# Easy_RFPA_RevA_S2.net
KiCad netlist of a schematic drawn in EAGLE
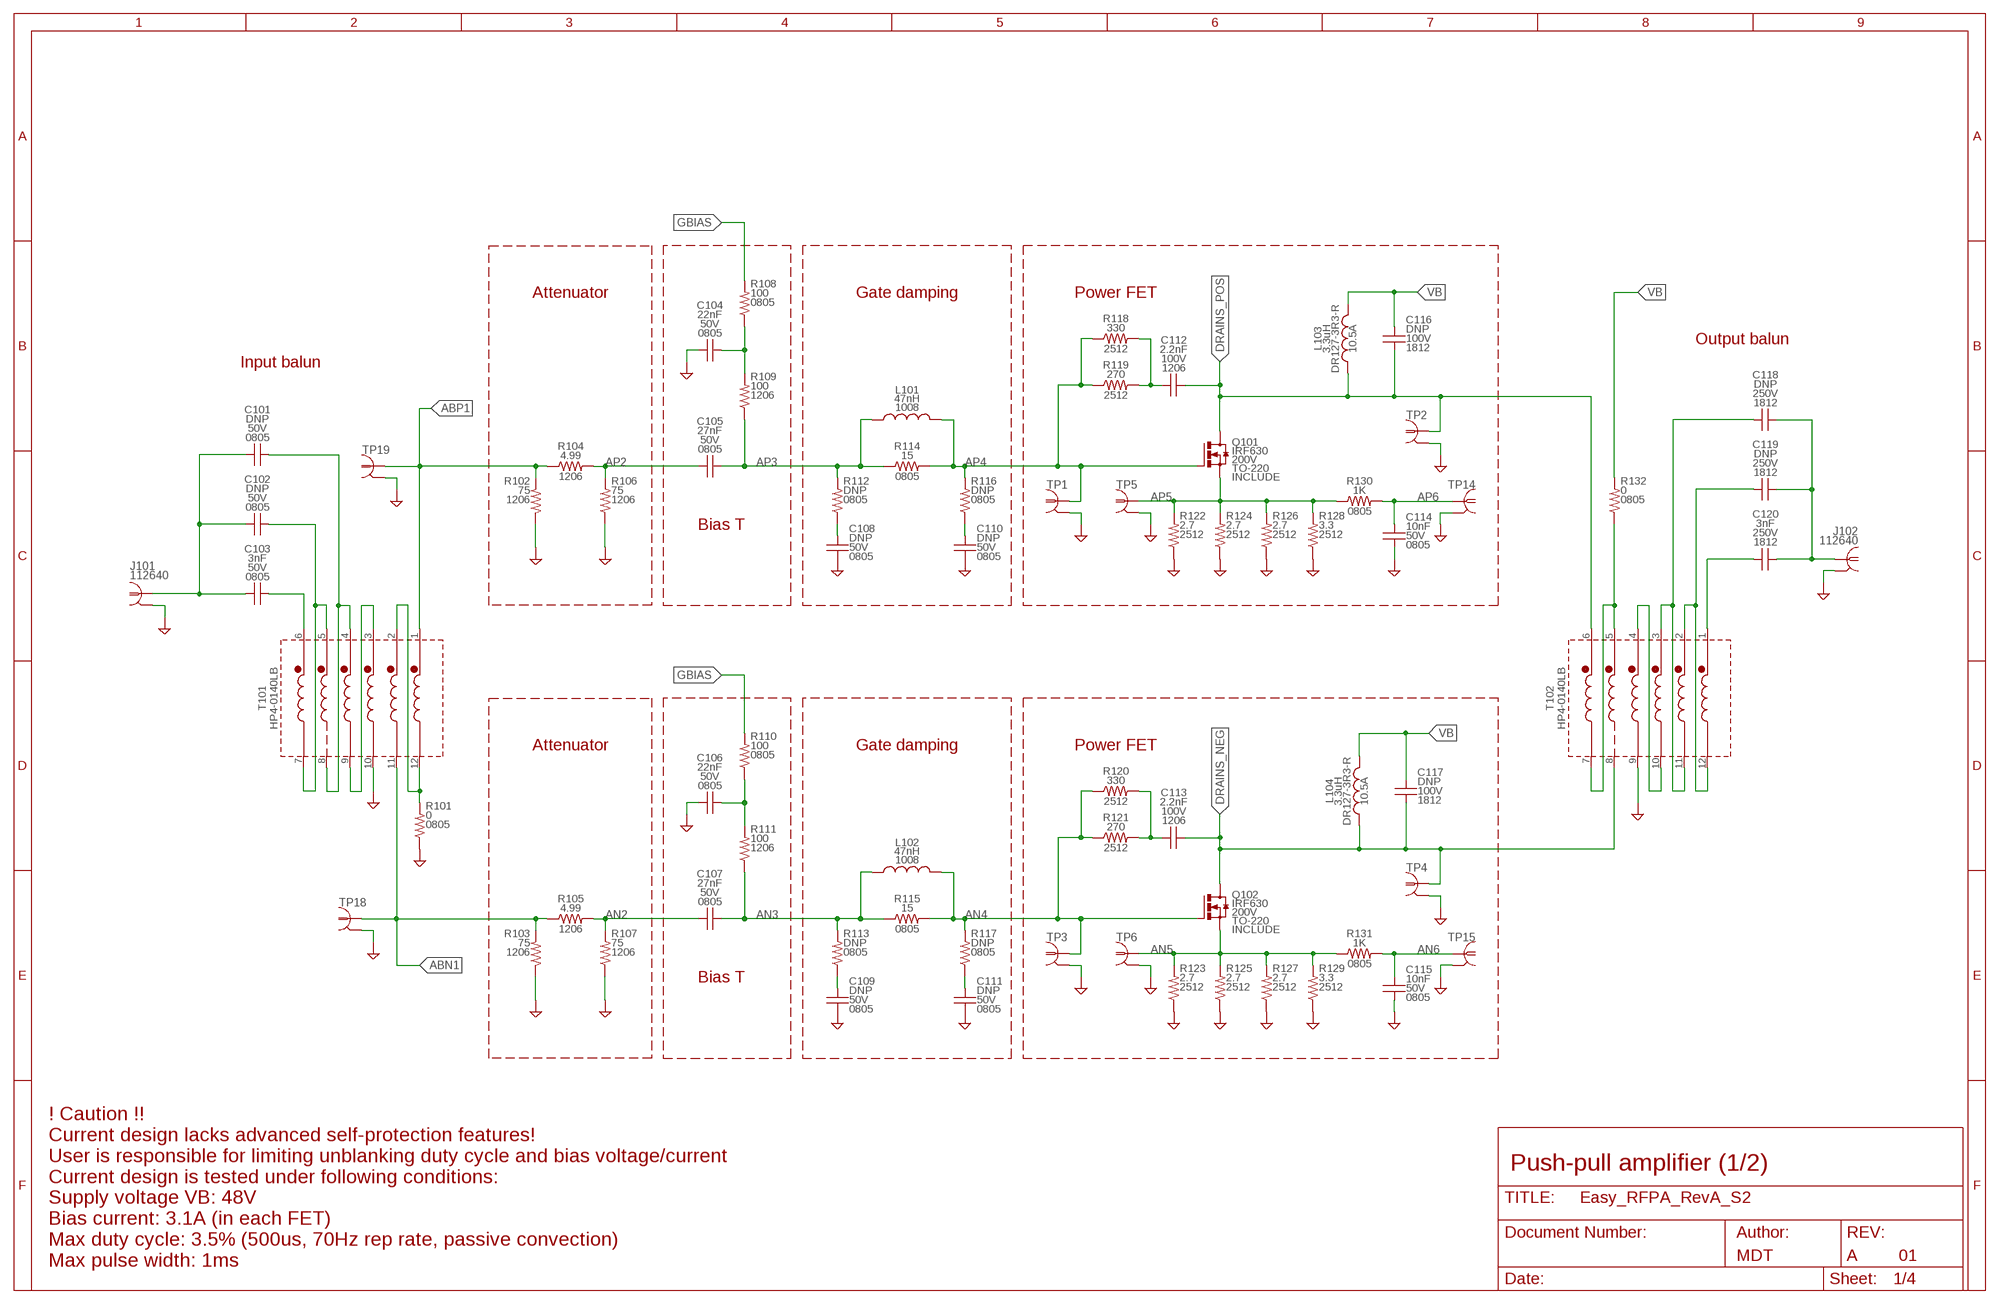
[diagram p0: schematic, sheet 1]
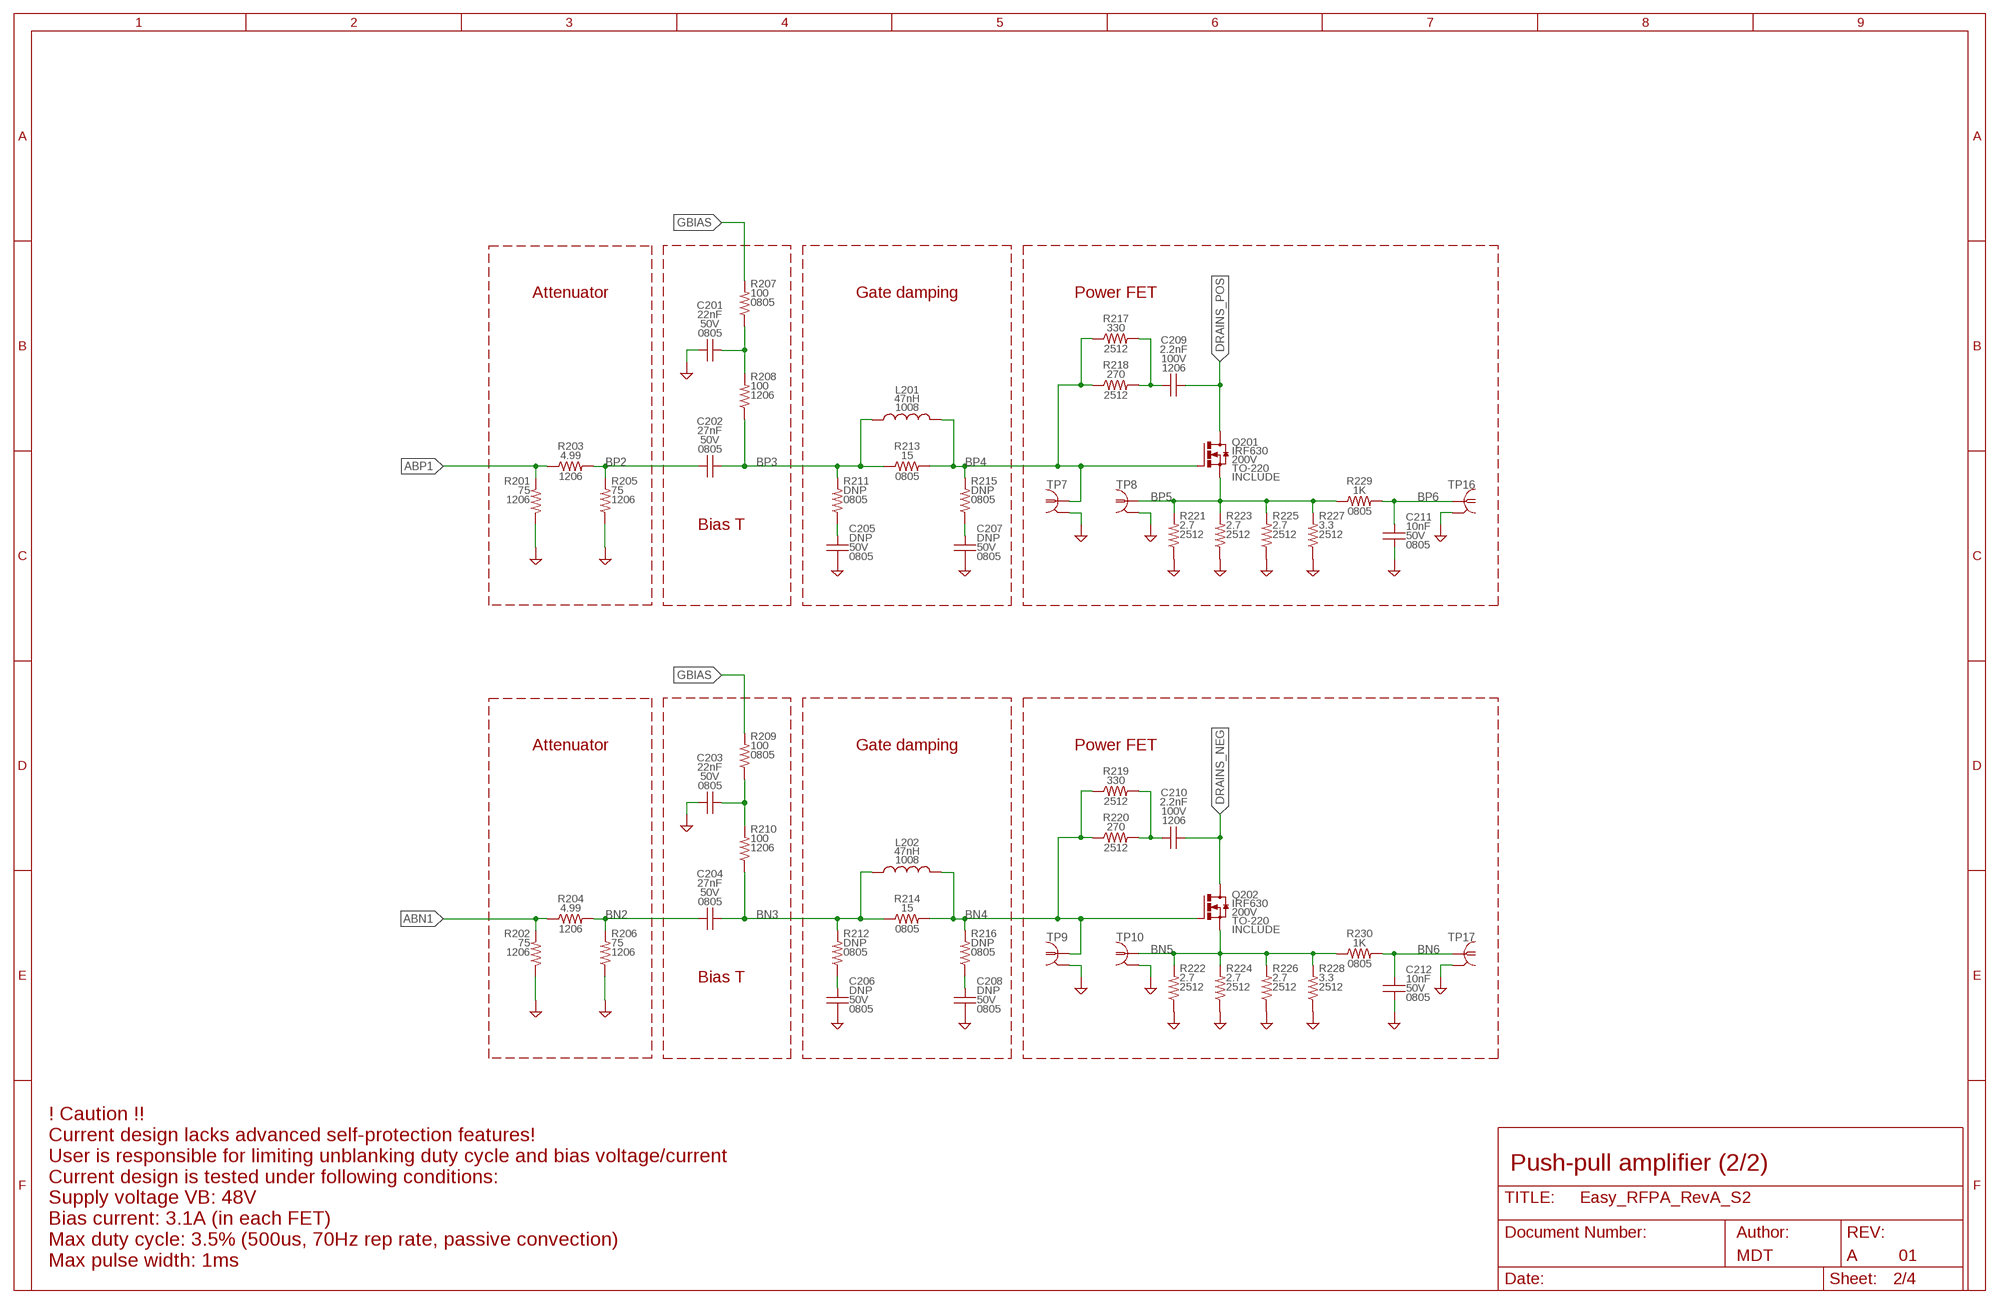
[diagram p1: schematic, sheet 2]
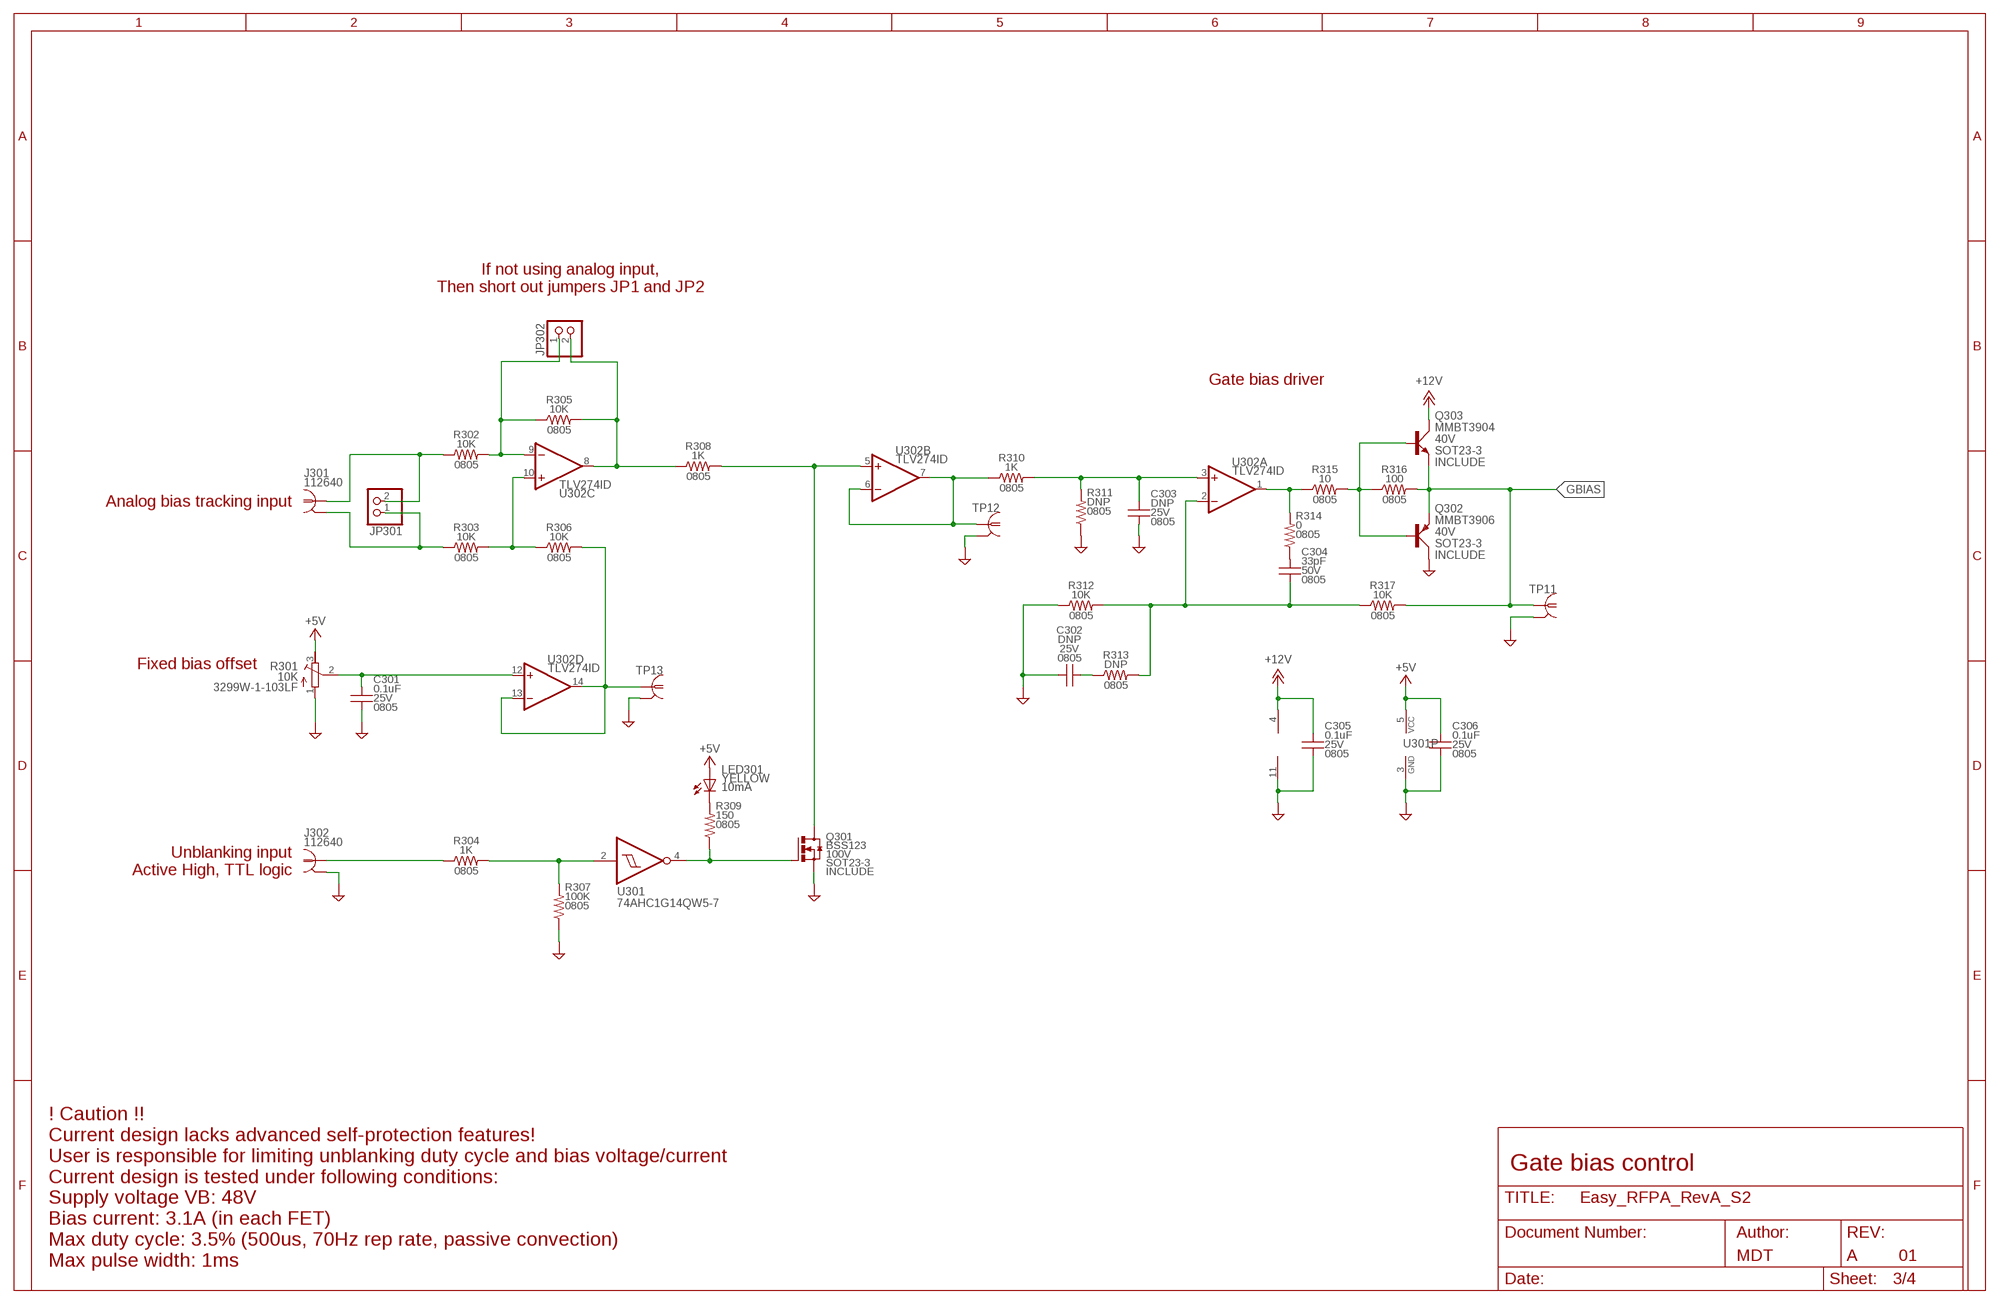
[diagram p2: schematic, sheet 3]
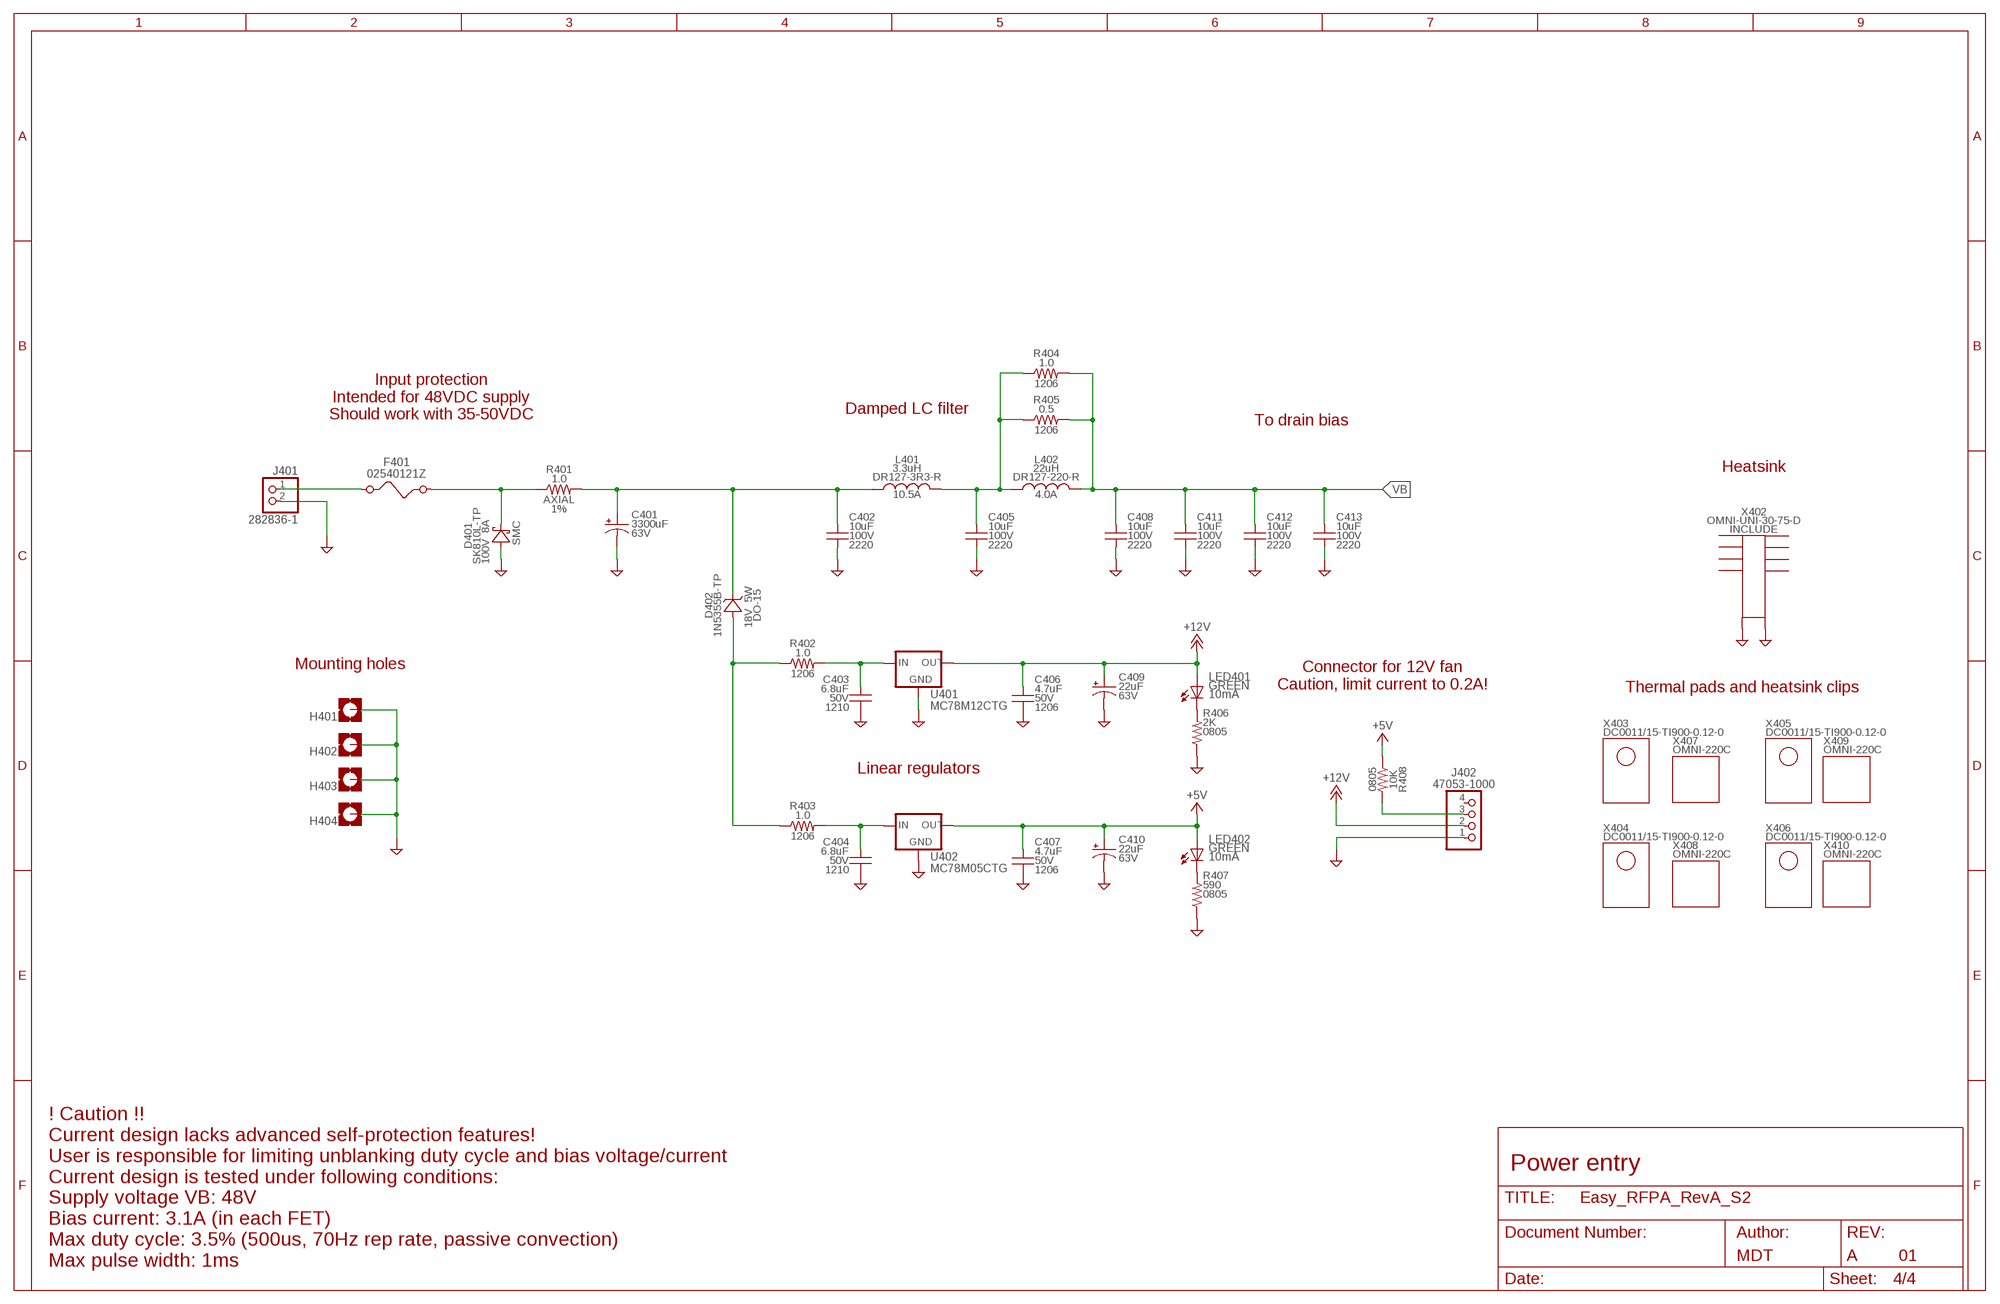
[diagram p3: schematic, sheet 4]

(export (version "E")
  (design (tool "Eeschema 10.0.6"))
  (components
    (comp (ref "C101")
      (value "DNP")
      (footprint "eagle-import:0805_IPC-7351B")
      (fields (field (name "PACKAGE") "0805") (field (name "BOM") "EXCLUDE") (field (name "VOLTAGE") "50V"))
      (libsource (lib "eagle-import") (part "C0805_IPCGEN"))
    )
    (comp (ref "C102")
      (value "DNP")
      (footprint "eagle-import:0805_IPC-7351B")
      (fields (field (name "PACKAGE") "0805") (field (name "BOM") "EXCLUDE") (field (name "VOLTAGE") "50V"))
      (libsource (lib "eagle-import") (part "C0805_IPCGEN"))
    )
    (comp (ref "C103")
      (value "3nF")
      (footprint "eagle-import:0805_IPC-7351B")
      (fields (field (name "PACKAGE") "0805") (field (name "VOLTAGE") "50V"))
      (libsource (lib "eagle-import") (part "C0805_IPCGEN"))
    )
    (comp (ref "C104")
      (value "22nF")
      (footprint "eagle-import:0805_IPC-7351B")
      (fields (field (name "BOM") "INCLUDE") (field (name "PACKAGE") "0805") (field (name "VOLTAGE") "50V"))
      (libsource (lib "eagle-import") (part "C0805_IPCGEN"))
    )
    (comp (ref "C105")
      (value "27nF")
      (footprint "eagle-import:0805_IPC-7351B")
      (fields (field (name "PACKAGE") "0805") (field (name "VOLTAGE") "50V"))
      (libsource (lib "eagle-import") (part "C0805_IPCGEN"))
    )
    (comp (ref "C106")
      (value "22nF")
      (footprint "eagle-import:0805_IPC-7351B")
      (fields (field (name "PACKAGE") "0805") (field (name "VOLTAGE") "50V"))
      (libsource (lib "eagle-import") (part "C0805_IPCGEN"))
    )
    (comp (ref "C107")
      (value "27nF")
      (footprint "eagle-import:0805_IPC-7351B")
      (fields (field (name "PACKAGE") "0805") (field (name "VOLTAGE") "50V"))
      (libsource (lib "eagle-import") (part "C0805_IPCGEN"))
    )
    (comp (ref "C108")
      (value "DNP")
      (footprint "eagle-import:0805_IPC-7351B")
      (fields (field (name "BOM") "EXCLUDE") (field (name "VOLTAGE") "50V"))
      (libsource (lib "eagle-import") (part "C0805_IPCGEN"))
    )
    (comp (ref "C109")
      (value "DNP")
      (footprint "eagle-import:0805_IPC-7351B")
      (fields (field (name "BOM") "EXCLUDE") (field (name "VOLTAGE") "50V"))
      (libsource (lib "eagle-import") (part "C0805_IPCGEN"))
    )
    (comp (ref "C110")
      (value "DNP")
      (footprint "eagle-import:0805_IPC-7351B")
      (fields (field (name "BOM") "EXCLUDE") (field (name "VOLTAGE") "50V"))
      (libsource (lib "eagle-import") (part "C0805_IPCGEN"))
    )
    (comp (ref "C111")
      (value "DNP")
      (footprint "eagle-import:0805_IPC-7351B")
      (fields (field (name "BOM") "EXCLUDE") (field (name "VOLTAGE") "50V"))
      (libsource (lib "eagle-import") (part "C0805_IPCGEN"))
    )
    (comp (ref "C112")
      (value "2.2nF")
      (footprint "eagle-import:C1206")
      (fields (field (name "PACKAGE") "1206") (field (name "VOLTAGE") "100V"))
      (libsource (lib "eagle-import") (part "CC1206GEN"))
    )
    (comp (ref "C113")
      (value "2.2nF")
      (footprint "eagle-import:C1206")
      (fields (field (name "PACKAGE") "1206") (field (name "VOLTAGE") "100V"))
      (libsource (lib "eagle-import") (part "CC1206GEN"))
    )
    (comp (ref "C114")
      (value "10nF")
      (footprint "eagle-import:0805_IPC-7351B")
      (fields (field (name "VOLTAGE") "50V"))
      (libsource (lib "eagle-import") (part "C0805_IPCGEN"))
    )
    (comp (ref "C115")
      (value "10nF")
      (footprint "eagle-import:0805_IPC-7351B")
      (fields (field (name "VOLTAGE") "50V"))
      (libsource (lib "eagle-import") (part "C0805_IPCGEN"))
    )
    (comp (ref "C116")
      (value "DNP")
      (footprint "eagle-import:C1812")
      (fields (field (name "BOM") "EXCLUDE") (field (name "VOLTAGE") "100V"))
      (libsource (lib "eagle-import") (part "CC1812GEN"))
    )
    (comp (ref "C117")
      (value "DNP")
      (footprint "eagle-import:C1812")
      (fields (field (name "BOM") "EXCLUDE") (field (name "VOLTAGE") "100V"))
      (libsource (lib "eagle-import") (part "CC1812GEN"))
    )
    (comp (ref "C118")
      (value "DNP")
      (footprint "eagle-import:C1812")
      (fields (field (name "PACKAGE") "1812") (field (name "BOM") "EXCLUDE") (field (name "VOLTAGE") "250V"))
      (libsource (lib "eagle-import") (part "CC1812GEN"))
    )
    (comp (ref "C119")
      (value "DNP")
      (footprint "eagle-import:C1812")
      (fields (field (name "PACKAGE") "1812") (field (name "BOM") "EXCLUDE") (field (name "VOLTAGE") "250V"))
      (libsource (lib "eagle-import") (part "CC1812GEN"))
    )
    (comp (ref "C120")
      (value "3nF")
      (footprint "eagle-import:C1812")
      (fields (field (name "PACKAGE") "1812") (field (name "VOLTAGE") "250V"))
      (libsource (lib "eagle-import") (part "CC1812GEN"))
    )
    (comp (ref "J101")
      (value "COAX112640BNC_EDGE")
      (footprint "eagle-import:BNC_EDGE")
      (fields (field (name "PARTNO") "112640"))
      (libsource (lib "eagle-import") (part "COAXBNC_EDGE112640"))
    )
    (comp (ref "J102")
      (value "COAX112640BNC_EDGE")
      (footprint "eagle-import:BNC_EDGE")
      (fields (field (name "PARTNO") "112640"))
      (libsource (lib "eagle-import") (part "COAXBNC_EDGE112640"))
    )
    (comp (ref "L101")
      (value "47nH")
      (footprint "eagle-import:L1008")
      (fields (field (name "PARTNO") "1008CS-470XJLC"))
      (libsource (lib "eagle-import") (part "L_CHIP1008L-47N-AIR-5%-1008-1A"))
    )
    (comp (ref "L102")
      (value "47nH")
      (footprint "eagle-import:L1008")
      (fields (field (name "PARTNO") "1008CS-470XJLC"))
      (libsource (lib "eagle-import") (part "L_CHIP1008L-47N-AIR-5%-1008-1A"))
    )
    (comp (ref "L103")
      (value "3.3uH")
      (footprint "eagle-import:DR127")
      (fields (field (name "PARTNO") "DR127-3R3-R"))
      (libsource (lib "eagle-import") (part "LL-3.3U-FERRITE-20%-12.5X12.5MM-10.5A"))
    )
    (comp (ref "L104")
      (value "3.3uH")
      (footprint "eagle-import:DR127")
      (fields (field (name "PARTNO") "DR127-3R3-R"))
      (libsource (lib "eagle-import") (part "LL-3.3U-FERRITE-20%-12.5X12.5MM-10.5A"))
    )
    (comp (ref "Q101")
      (value "IRF630")
      (footprint "eagle-import:TO220BV")
      (fields (field (name "VOLTAGE") "200V"))
      (libsource (lib "eagle-import") (part "MOSFET_NTO-220-VERTIRF630"))
    )
    (comp (ref "Q102")
      (value "IRF630")
      (footprint "eagle-import:TO220BV")
      (fields (field (name "VOLTAGE") "200V"))
      (libsource (lib "eagle-import") (part "MOSFET_NTO-220-VERTIRF630"))
    )
    (comp (ref "R101")
      (value "0")
      (footprint "eagle-import:0805_IPC-7351B")
      (libsource (lib "eagle-import") (part "R0805_IPCGEN"))
    )
    (comp (ref "R102")
      (value "75")
      (footprint "eagle-import:1206_IPC-7351B")
      (libsource (lib "eagle-import") (part "R1206_IPCGEN"))
    )
    (comp (ref "R103")
      (value "75")
      (footprint "eagle-import:1206_IPC-7351B")
      (libsource (lib "eagle-import") (part "R1206_IPCGEN"))
    )
    (comp (ref "R104")
      (value "4.99")
      (footprint "eagle-import:1206_IPC-7351B")
      (libsource (lib "eagle-import") (part "R901206_IPCGEN"))
    )
    (comp (ref "R105")
      (value "4.99")
      (footprint "eagle-import:1206_IPC-7351B")
      (libsource (lib "eagle-import") (part "R901206_IPCGEN"))
    )
    (comp (ref "R106")
      (value "75")
      (footprint "eagle-import:1206_IPC-7351B")
      (libsource (lib "eagle-import") (part "R1206_IPCGEN"))
    )
    (comp (ref "R107")
      (value "75")
      (footprint "eagle-import:1206_IPC-7351B")
      (libsource (lib "eagle-import") (part "R1206_IPCGEN"))
    )
    (comp (ref "R108")
      (value "100")
      (footprint "eagle-import:0805_IPC-7351B")
      (libsource (lib "eagle-import") (part "R0805_IPCGEN"))
    )
    (comp (ref "R109")
      (value "100")
      (footprint "eagle-import:1206_IPC-7351B")
      (libsource (lib "eagle-import") (part "R1206_IPCGEN"))
    )
    (comp (ref "R110")
      (value "100")
      (footprint "eagle-import:0805_IPC-7351B")
      (libsource (lib "eagle-import") (part "R0805_IPCGEN"))
    )
    (comp (ref "R111")
      (value "100")
      (footprint "eagle-import:1206_IPC-7351B")
      (libsource (lib "eagle-import") (part "R1206_IPCGEN"))
    )
    (comp (ref "R112")
      (value "DNP")
      (footprint "eagle-import:0805_IPC-7351B")
      (fields (field (name "BOM") "EXCLUDE"))
      (libsource (lib "eagle-import") (part "R0805_IPCGEN"))
    )
    (comp (ref "R113")
      (value "DNP")
      (footprint "eagle-import:0805_IPC-7351B")
      (fields (field (name "BOM") "EXCLUDE"))
      (libsource (lib "eagle-import") (part "R0805_IPCGEN"))
    )
    (comp (ref "R114")
      (value "15")
      (footprint "eagle-import:0805_IPC-7351B")
      (libsource (lib "eagle-import") (part "R900805_IPCGEN"))
    )
    (comp (ref "R115")
      (value "15")
      (footprint "eagle-import:0805_IPC-7351B")
      (libsource (lib "eagle-import") (part "R900805_IPCGEN"))
    )
    (comp (ref "R116")
      (value "DNP")
      (footprint "eagle-import:0805_IPC-7351B")
      (fields (field (name "BOM") "EXCLUDE"))
      (libsource (lib "eagle-import") (part "R0805_IPCGEN"))
    )
    (comp (ref "R117")
      (value "DNP")
      (footprint "eagle-import:0805_IPC-7351B")
      (fields (field (name "BOM") "EXCLUDE"))
      (libsource (lib "eagle-import") (part "R0805_IPCGEN"))
    )
    (comp (ref "R118")
      (value "330")
      (footprint "eagle-import:R2512")
      (libsource (lib "eagle-import") (part "R90R2512GEN"))
    )
    (comp (ref "R119")
      (value "270")
      (footprint "eagle-import:R2512")
      (libsource (lib "eagle-import") (part "R90R2512GEN"))
    )
    (comp (ref "R120")
      (value "330")
      (footprint "eagle-import:R2512")
      (libsource (lib "eagle-import") (part "R90R2512GEN"))
    )
    (comp (ref "R121")
      (value "270")
      (footprint "eagle-import:R2512")
      (libsource (lib "eagle-import") (part "R90R2512GEN"))
    )
    (comp (ref "R122")
      (value "2.7")
      (footprint "eagle-import:R2512")
      (libsource (lib "eagle-import") (part "RR2512GEN"))
    )
    (comp (ref "R123")
      (value "2.7")
      (footprint "eagle-import:R2512")
      (libsource (lib "eagle-import") (part "RR2512GEN"))
    )
    (comp (ref "R124")
      (value "2.7")
      (footprint "eagle-import:R2512")
      (libsource (lib "eagle-import") (part "RR2512GEN"))
    )
    (comp (ref "R125")
      (value "2.7")
      (footprint "eagle-import:R2512")
      (libsource (lib "eagle-import") (part "RR2512GEN"))
    )
    (comp (ref "R126")
      (value "2.7")
      (footprint "eagle-import:R2512")
      (libsource (lib "eagle-import") (part "RR2512GEN"))
    )
    (comp (ref "R127")
      (value "2.7")
      (footprint "eagle-import:R2512")
      (libsource (lib "eagle-import") (part "RR2512GEN"))
    )
    (comp (ref "R128")
      (value "3.3")
      (footprint "eagle-import:R2512")
      (libsource (lib "eagle-import") (part "RR2512GEN"))
    )
    (comp (ref "R129")
      (value "3.3")
      (footprint "eagle-import:R2512")
      (libsource (lib "eagle-import") (part "RR2512GEN"))
    )
    (comp (ref "R130")
      (value "1K")
      (footprint "eagle-import:0805_IPC-7351B")
      (libsource (lib "eagle-import") (part "R900805_IPCGEN"))
    )
    (comp (ref "R131")
      (value "1K")
      (footprint "eagle-import:0805_IPC-7351B")
      (libsource (lib "eagle-import") (part "R900805_IPCGEN"))
    )
    (comp (ref "R132")
      (value "0")
      (footprint "eagle-import:0805_IPC-7351B")
      (libsource (lib "eagle-import") (part "R0805_IPCGEN"))
    )
    (comp (ref "T101")
      (value "HP4_TRAFO")
      (footprint "eagle-import:HP4")
      (fields (field (name "PARTNO") "HP4-0140LB"))
      (libsource (lib "eagle-import") (part "HP4_TRAFO"))
    )
    (comp (ref "T102")
      (value "HP4_TRAFO")
      (footprint "eagle-import:HP4")
      (fields (field (name "PARTNO") "HP4-0140LB"))
      (libsource (lib "eagle-import") (part "HP4_TRAFO"))
    )
    (comp (ref "TP1")
      (value "PROBE_TPTP_5MM")
      (footprint "eagle-import:PROBE_TP_5MM")
      (libsource (lib "eagle-import") (part "PROBE_TPTP_5MM"))
    )
    (comp (ref "TP2")
      (value "PROBE_TPTP_7P5MM")
      (footprint "eagle-import:PROBE_TP_7P5MM")
      (libsource (lib "eagle-import") (part "PROBE_TPTP_7P5MM"))
    )
    (comp (ref "TP3")
      (value "PROBE_TPTP_5MM")
      (footprint "eagle-import:PROBE_TP_5MM")
      (libsource (lib "eagle-import") (part "PROBE_TPTP_5MM"))
    )
    (comp (ref "TP4")
      (value "PROBE_TPTP_7P5MM")
      (footprint "eagle-import:PROBE_TP_7P5MM")
      (libsource (lib "eagle-import") (part "PROBE_TPTP_7P5MM"))
    )
    (comp (ref "TP5")
      (value "PROBE_TPTP_7P5MM")
      (footprint "eagle-import:PROBE_TP_7P5MM")
      (libsource (lib "eagle-import") (part "PROBE_TPTP_7P5MM"))
    )
    (comp (ref "TP6")
      (value "PROBE_TPTP_7P5MM")
      (footprint "eagle-import:PROBE_TP_7P5MM")
      (libsource (lib "eagle-import") (part "PROBE_TPTP_7P5MM"))
    )
    (comp (ref "TP14")
      (value "PROBE_TPTP_5MM")
      (footprint "eagle-import:PROBE_TP_5MM")
      (libsource (lib "eagle-import") (part "PROBE_TPTP_5MM"))
    )
    (comp (ref "TP15")
      (value "PROBE_TPTP_5MM")
      (footprint "eagle-import:PROBE_TP_5MM")
      (libsource (lib "eagle-import") (part "PROBE_TPTP_5MM"))
    )
    (comp (ref "TP18")
      (value "PROBE_TPTP_5MM")
      (footprint "eagle-import:PROBE_TP_5MM")
      (libsource (lib "eagle-import") (part "PROBE_TPTP_5MM"))
    )
    (comp (ref "TP19")
      (value "PROBE_TPTP_5MM")
      (footprint "eagle-import:PROBE_TP_5MM")
      (libsource (lib "eagle-import") (part "PROBE_TPTP_5MM"))
    )
    (comp (ref "C401")
      (value "3300uF")
      (footprint "eagle-import:EB25D")
      (fields (field (name "PARTNO") "MAL225638332E3") (field (name "VOLTAGE") "63V"))
      (libsource (lib "eagle-import") (part "CPOLEB25DC-3300U-63V-20%-25DX37L-ELEC"))
    )
    (comp (ref "C402")
      (value "10uF")
      (footprint "eagle-import:C2220_CKG57N")
      (fields
        (field (name "BOM") "INCLUDE")
        (field (name "PACKAGE") "2220")
        (field (name "PARTNO") "CGA9N3X7S2A106M230KE")
        (field (name "VOLTAGE") "100V")
      )
      (libsource (lib "eagle-import") (part "CC2220_CKG57NCC-10U-100V-20%-2220-X7T"))
    )
    (comp (ref "C403")
      (value "6.8uF")
      (footprint "eagle-import:C1210")
      (fields (field (name "DIALECTRIC") "X7S") (field (name "VOLTAGE") "50V"))
      (libsource (lib "eagle-import") (part "CC1210GEN"))
    )
    (comp (ref "C404")
      (value "6.8uF")
      (footprint "eagle-import:C1210")
      (fields (field (name "DIALECTRIC") "X7S") (field (name "VOLTAGE") "50V"))
      (libsource (lib "eagle-import") (part "CC1210GEN"))
    )
    (comp (ref "C405")
      (value "10uF")
      (footprint "eagle-import:C2220_CKG57N")
      (fields
        (field (name "BOM") "INCLUDE")
        (field (name "PACKAGE") "2220")
        (field (name "PARTNO") "CGA9N3X7S2A106M230KE")
        (field (name "VOLTAGE") "100V")
      )
      (libsource (lib "eagle-import") (part "CC2220_CKG57NCC-10U-100V-20%-2220-X7T"))
    )
    (comp (ref "C406")
      (value "4.7uF")
      (footprint "eagle-import:C1206")
      (fields (field (name "DIALECTRIC") "X7R") (field (name "VOLTAGE") "50V"))
      (libsource (lib "eagle-import") (part "CC1206GEN"))
    )
    (comp (ref "C407")
      (value "4.7uF")
      (footprint "eagle-import:C1206")
      (fields (field (name "DIALECTRIC") "X7R") (field (name "VOLTAGE") "50V"))
      (libsource (lib "eagle-import") (part "CC1206GEN"))
    )
    (comp (ref "C408")
      (value "10uF")
      (footprint "eagle-import:C2220_CKG57N")
      (fields (field (name "PARTNO") "CGA9N3X7S2A106M230KE") (field (name "VOLTAGE") "100V"))
      (libsource (lib "eagle-import") (part "CC2220_CKG57NCC-10U-100V-20%-2220-X7T"))
    )
    (comp (ref "C409")
      (value "22uF")
      (footprint "eagle-import:E2,5-7")
      (fields (field (name "PARTNO") "860010773010") (field (name "VOLTAGE") "63V"))
      (libsource (lib "eagle-import") (part "CPOLE2,5-7C-22U-63V-20%-6.3DX12.5L-ELEC"))
    )
    (comp (ref "C410")
      (value "22uF")
      (footprint "eagle-import:E2,5-7")
      (fields (field (name "PARTNO") "860010773010") (field (name "VOLTAGE") "63V"))
      (libsource (lib "eagle-import") (part "CPOLE2,5-7C-22U-63V-20%-6.3DX12.5L-ELEC"))
    )
    (comp (ref "C411")
      (value "10uF")
      (footprint "eagle-import:C2220_CKG57N")
      (fields (field (name "PARTNO") "CGA9N3X7S2A106M230KE") (field (name "VOLTAGE") "100V"))
      (libsource (lib "eagle-import") (part "CC2220_CKG57NCC-10U-100V-20%-2220-X7T"))
    )
    (comp (ref "C412")
      (value "10uF")
      (footprint "eagle-import:C2220_CKG57N")
      (fields (field (name "PARTNO") "CGA9N3X7S2A106M230KE") (field (name "VOLTAGE") "100V"))
      (libsource (lib "eagle-import") (part "CC2220_CKG57NCC-10U-100V-20%-2220-X7T"))
    )
    (comp (ref "C413")
      (value "10uF")
      (footprint "eagle-import:C2220_CKG57N")
      (fields (field (name "PARTNO") "CGA9N3X7S2A106M230KE") (field (name "VOLTAGE") "100V"))
      (libsource (lib "eagle-import") (part "CC2220_CKG57NCC-10U-100V-20%-2220-X7T"))
    )
    (comp (ref "D401")
      (value "D-SCHOTTKYSK810L-TPSMC")
      (footprint "eagle-import:DO-214AB(SMC)")
      (fields (field (name "PARTNO") "SK810L-TP") (field (name "VOLTAGE") "100V"))
      (libsource (lib "eagle-import") (part "D-SCHOTTKYSMCSK810L-TP"))
    )
    (comp (ref "D402")
      (value "D-ZENER1N5355B-TPDO15-12")
      (footprint "eagle-import:DO15-12")
      (fields (field (name "PARTNO") "1N5355B-TP") (field (name "POWER") "5W") (field (name "VOLTAGE") "18V"))
      (libsource (lib "eagle-import") (part "D-ZENERDO15-121N5355B-TP"))
    )
    (comp (ref "F401")
      (value "FUSE_2P")
      (footprint "eagle-import:02540121Z")
      (fields (field (name "PARTNO") "02540121Z"))
      (libsource (lib "eagle-import") (part "FUSE_2P"))
    )
    (comp (ref "H401")
      (value "MOUNT-PAD-SQUARE3.2")
      (footprint "eagle-import:3,2-PAD-SQUARE")
      (libsource (lib "eagle-import") (part "MOUNT-PAD-SQUARE3.2"))
    )
    (comp (ref "H402")
      (value "MOUNT-PAD-SQUARE3.2")
      (footprint "eagle-import:3,2-PAD-SQUARE")
      (libsource (lib "eagle-import") (part "MOUNT-PAD-SQUARE3.2"))
    )
    (comp (ref "H403")
      (value "MOUNT-PAD-SQUARE3.2")
      (footprint "eagle-import:3,2-PAD-SQUARE")
      (libsource (lib "eagle-import") (part "MOUNT-PAD-SQUARE3.2"))
    )
    (comp (ref "H404")
      (value "MOUNT-PAD-SQUARE3.2")
      (footprint "eagle-import:3,2-PAD-SQUARE")
      (libsource (lib "eagle-import") (part "MOUNT-PAD-SQUARE3.2"))
    )
    (comp (ref "J401")
      (value "HDR_2X1282836-1282836-1")
      (footprint "eagle-import:W237-02")
      (fields (field (name "PARTNO") "282836-1"))
      (libsource (lib "eagle-import") (part "HDR_2X1282836-1282836-1"))
    )
    (comp (ref "J402")
      (value "KK_PCFAN")
      (footprint "eagle-import:47053-1000")
      (fields (field (name "PARTNO") "47053-1000"))
      (libsource (lib "eagle-import") (part "KK_PCFAN"))
    )
    (comp (ref "L401")
      (value "3.3uH")
      (footprint "eagle-import:DR127")
      (fields (field (name "PARTNO") "DR127-3R3-R"))
      (libsource (lib "eagle-import") (part "LL-3.3U-FERRITE-20%-12.5X12.5MM-10.5A"))
    )
    (comp (ref "L402")
      (value "22uH")
      (footprint "eagle-import:DR127")
      (fields (field (name "PARTNO") "DR127-220-R"))
      (libsource (lib "eagle-import") (part "LL-22U-FERRITE-20%-12.5X12.5MM-4A"))
    )
    (comp (ref "LED401")
      (value "LEDHLMP-3962-F0002T1_3/4")
      (footprint "eagle-import:LED5MM")
      (fields (field (name "PARTNO") "HLMP-3962-F0002"))
      (libsource (lib "eagle-import") (part "LEDT1_3/4HLMP-3962-F0002"))
    )
    (comp (ref "LED402")
      (value "LEDHLMP-3962-F0002T1_3/4")
      (footprint "eagle-import:LED5MM")
      (fields (field (name "PARTNO") "HLMP-3962-F0002"))
      (libsource (lib "eagle-import") (part "LEDT1_3/4HLMP-3962-F0002"))
    )
    (comp (ref "R401")
      (value "1.0")
      (footprint "eagle-import:P0817V")
      (fields (field (name "PARTNO") "PAC300001008FAC000") (field (name "POWER") "3W"))
      (libsource (lib "eagle-import") (part "R90P0817VR-1.0-1%-AXIAL-3W"))
    )
    (comp (ref "R402")
      (value "1.0")
      (footprint "eagle-import:R1206")
      (libsource (lib "eagle-import") (part "R90R1206GEN"))
    )
    (comp (ref "R403")
      (value "1.0")
      (footprint "eagle-import:R1206")
      (libsource (lib "eagle-import") (part "R90R1206GEN"))
    )
    (comp (ref "R404")
      (value "1.0")
      (footprint "eagle-import:1206_IPC-7351B")
      (libsource (lib "eagle-import") (part "R901206_IPCGEN"))
    )
    (comp (ref "R405")
      (value "0.5")
      (footprint "eagle-import:1206_IPC-7351B")
      (libsource (lib "eagle-import") (part "R901206_IPCGEN"))
    )
    (comp (ref "R406")
      (value "2K")
      (footprint "eagle-import:0805_IPC-7351B")
      (libsource (lib "eagle-import") (part "R0805_IPCGEN"))
    )
    (comp (ref "R407")
      (value "590")
      (footprint "eagle-import:0805_IPC-7351B")
      (libsource (lib "eagle-import") (part "R0805_IPCGEN"))
    )
    (comp (ref "R408")
      (value "10K")
      (footprint "eagle-import:0805_IPC-7351B")
      (libsource (lib "eagle-import") (part "R900805_IPCGEN"))
    )
    (comp (ref "U401")
      (value "LDO_3TERMMC78M12CTGTO220_VERT")
      (footprint "eagle-import:TO220BV")
      (fields (field (name "PARTNO") "MC78M12CTG"))
      (libsource (lib "eagle-import") (part "LDO_3TERMTO220_VERTMC78M12CTG"))
    )
    (comp (ref "U402")
      (value "LDO_3TERMMC78M05CTGTO220_VERT")
      (footprint "eagle-import:TO220BV")
      (fields (field (name "PARTNO") "MC78M05CTG"))
      (libsource (lib "eagle-import") (part "LDO_3TERMTO220_VERTMC78M05CTG"))
    )
    (comp (ref "X402")
      (value "HEATSINK_OMNI_DUALOMNI-UNI-30-75-D30-75-D")
      (footprint "eagle-import:OMNI-UNI-30-75-D")
      (fields (field (name "PARTNO") "OMNI-UNI-30-75-D"))
      (libsource (lib "eagle-import") (part "HEATSINK_OMNI_DUAL30-75-DOMNI-UNI-30-75-D"))
    )
    (comp (ref "C301")
      (value "0.1uF")
      (footprint "eagle-import:0805_IPC-7351B")
      (fields (field (name "VOLTAGE") "25V"))
      (libsource (lib "eagle-import") (part "C0805_IPCGEN"))
    )
    (comp (ref "C302")
      (value "DNP")
      (footprint "eagle-import:0805_IPC-7351B")
      (fields (field (name "PACKAGE") "0805") (field (name "BOM") "EXCLUDE") (field (name "VOLTAGE") "25V"))
      (libsource (lib "eagle-import") (part "C0805_IPCGEN"))
    )
    (comp (ref "C303")
      (value "DNP")
      (footprint "eagle-import:0805_IPC-7351B")
      (fields (field (name "BOM") "EXCLUDE") (field (name "VOLTAGE") "25V"))
      (libsource (lib "eagle-import") (part "C0805_IPCGEN"))
    )
    (comp (ref "C304")
      (value "33pF")
      (footprint "eagle-import:0805_IPC-7351B")
      (fields (field (name "VOLTAGE") "50V"))
      (libsource (lib "eagle-import") (part "C0805_IPCGEN"))
    )
    (comp (ref "C305")
      (value "0.1uF")
      (footprint "eagle-import:0805_IPC-7351B")
      (fields (field (name "VOLTAGE") "25V"))
      (libsource (lib "eagle-import") (part "C0805_IPCGEN"))
    )
    (comp (ref "C306")
      (value "0.1uF")
      (footprint "eagle-import:0805_IPC-7351B")
      (fields (field (name "VOLTAGE") "25V"))
      (libsource (lib "eagle-import") (part "C0805_IPCGEN"))
    )
    (comp (ref "J301")
      (value "COAX112640BNC_EDGE")
      (footprint "eagle-import:BNC_EDGE")
      (fields (field (name "PARTNO") "112640"))
      (libsource (lib "eagle-import") (part "COAXBNC_EDGE112640"))
    )
    (comp (ref "J302")
      (value "COAX112640BNC_EDGE")
      (footprint "eagle-import:BNC_EDGE")
      (fields (field (name "PARTNO") "112640"))
      (libsource (lib "eagle-import") (part "COAXBNC_EDGE112640"))
    )
    (comp (ref "JP301")
      (value "PINHD-1X2")
      (footprint "eagle-import:1X02")
      (libsource (lib "eagle-import") (part "PINHD-1X2"))
    )
    (comp (ref "JP302")
      (value "PINHD-1X2")
      (footprint "eagle-import:1X02")
      (libsource (lib "eagle-import") (part "PINHD-1X2"))
    )
    (comp (ref "LED301")
      (value "LEDHLMP-3401-E0002T1_3/4")
      (footprint "eagle-import:LED5MM")
      (fields (field (name "PARTNO") " HLMP-3401-E0002"))
      (libsource (lib "eagle-import") (part "LEDT1_3/4HLMP-3401-E0002"))
    )
    (comp (ref "Q301")
      (value "MOSFET_NBSS123SOT23")
      (footprint "eagle-import:SOT23R_INFINEON")
      (fields (field (name "PARTNO") "BSS123-7-F") (field (name "VOLTAGE") "100V"))
      (libsource (lib "eagle-import") (part "MOSFET_NSOT23BSS123"))
    )
    (comp (ref "Q302")
      (value "PNPSOT23_BEC")
      (footprint "eagle-import:SOT23R_INFINEON")
      (fields (field (name "VOLTAGE") "40V") (field (name "PARTNO") "PMBT3906,215"))
      (libsource (lib "eagle-import") (part "PNPSOT23_BEC"))
    )
    (comp (ref "Q303")
      (value "NPNMMBT3904SOT23_BEC")
      (footprint "eagle-import:SOT23R_INFINEON")
      (fields (field (name "PARTNO") "MMBT3904,215") (field (name "VOLTAGE") "40V"))
      (libsource (lib "eagle-import") (part "NPNSOT23_BECMMBT3904"))
    )
    (comp (ref "R301")
      (value "10K")
      (footprint "eagle-import:RTRIM3299W")
      (fields (field (name "PARTNO") "3299W-1-103LF") (field (name "POWER") "0.5W"))
      (libsource (lib "eagle-import") (part "RTRIM3299WRTRIM-10K-10%-3299W-0.5W"))
    )
    (comp (ref "R302")
      (value "10K")
      (footprint "eagle-import:0805_IPC-7351B")
      (libsource (lib "eagle-import") (part "R900805_IPCGEN"))
    )
    (comp (ref "R303")
      (value "10K")
      (footprint "eagle-import:0805_IPC-7351B")
      (libsource (lib "eagle-import") (part "R900805_IPCGEN"))
    )
    (comp (ref "R304")
      (value "1K")
      (footprint "eagle-import:0805_IPC-7351B")
      (libsource (lib "eagle-import") (part "R900805_IPCGEN"))
    )
    (comp (ref "R305")
      (value "10K")
      (footprint "eagle-import:0805_IPC-7351B")
      (libsource (lib "eagle-import") (part "R900805_IPCGEN"))
    )
    (comp (ref "R306")
      (value "10K")
      (footprint "eagle-import:0805_IPC-7351B")
      (libsource (lib "eagle-import") (part "R900805_IPCGEN"))
    )
    (comp (ref "R307")
      (value "100K")
      (footprint "eagle-import:0805_IPC-7351B")
      (libsource (lib "eagle-import") (part "R0805_IPCGEN"))
    )
    (comp (ref "R308")
      (value "1K")
      (footprint "eagle-import:0805_IPC-7351B")
      (libsource (lib "eagle-import") (part "R900805_IPCGEN"))
    )
    (comp (ref "R309")
      (value "150")
      (footprint "eagle-import:0805_IPC-7351B")
      (libsource (lib "eagle-import") (part "R0805_IPCGEN"))
    )
    (comp (ref "R310")
      (value "1K")
      (footprint "eagle-import:0805_IPC-7351B")
      (libsource (lib "eagle-import") (part "R900805_IPCGEN"))
    )
    (comp (ref "R311")
      (value "DNP")
      (footprint "eagle-import:0805_IPC-7351B")
      (fields (field (name "BOM") "EXCLUDE"))
      (libsource (lib "eagle-import") (part "R0805_IPCGEN"))
    )
    (comp (ref "R312")
      (value "10K")
      (footprint "eagle-import:0805_IPC-7351B")
      (libsource (lib "eagle-import") (part "R900805_IPCGEN"))
    )
    (comp (ref "R313")
      (value "DNP")
      (footprint "eagle-import:0805_IPC-7351B")
      (fields (field (name "BOM") "EXCLUDE"))
      (libsource (lib "eagle-import") (part "R900805_IPCGEN"))
    )
    (comp (ref "R314")
      (value "0")
      (footprint "eagle-import:0805_IPC-7351B")
      (libsource (lib "eagle-import") (part "R0805_IPCGEN"))
    )
    (comp (ref "R315")
      (value "10")
      (footprint "eagle-import:0805_IPC-7351B")
      (libsource (lib "eagle-import") (part "R900805_IPCGEN"))
    )
    (comp (ref "R316")
      (value "100")
      (footprint "eagle-import:0805_IPC-7351B")
      (libsource (lib "eagle-import") (part "R900805_IPCGEN"))
    )
    (comp (ref "R317")
      (value "10K")
      (footprint "eagle-import:0805_IPC-7351B")
      (libsource (lib "eagle-import") (part "R900805_IPCGEN"))
    )
    (comp (ref "TP11")
      (value "PROBE_TPTP_5MM")
      (footprint "eagle-import:PROBE_TP_5MM")
      (libsource (lib "eagle-import") (part "PROBE_TPTP_5MM"))
    )
    (comp (ref "TP12")
      (value "PROBE_TPTP_5MM")
      (footprint "eagle-import:PROBE_TP_5MM")
      (libsource (lib "eagle-import") (part "PROBE_TPTP_5MM"))
    )
    (comp (ref "TP13")
      (value "PROBE_TPTP_5MM")
      (footprint "eagle-import:PROBE_TP_5MM")
      (libsource (lib "eagle-import") (part "PROBE_TPTP_5MM"))
    )
    (comp (ref "U301")
      (value "74AHC1G14DBV")
      (footprint "eagle-import:SOT23-5")
      (description "IC INVERT SCHMITT 1CH 1-IN SOT25")
      (fields
        (field (name "PARTNO") "74AHC1G14QW5-7")
        (field (name "BOM") "INCLUDE")
        (field (name "PACKAGE") "SOT23-5")
        (field (name "VENDOR") "Diodes Inc")
      )
      (libsource (lib "eagle-import") (part "741G14DBVAHC"))
    )
    (comp (ref "U302")
      (value "OPAMP_QUADTLV274IDSOIC14")
      (footprint "eagle-import:SO14")
      (fields (field (name "PARTNO") "TLV274ID"))
      (libsource (lib "eagle-import") (part "OPAMP_QUADSOIC14TLV274ID"))
    )
    (comp (ref "C201")
      (value "22nF")
      (footprint "eagle-import:0805_IPC-7351B")
      (fields (field (name "PACKAGE") "0805") (field (name "VOLTAGE") "50V"))
      (libsource (lib "eagle-import") (part "C0805_IPCGEN"))
    )
    (comp (ref "C202")
      (value "27nF")
      (footprint "eagle-import:0805_IPC-7351B")
      (fields (field (name "PACKAGE") "0805") (field (name "VOLTAGE") "50V"))
      (libsource (lib "eagle-import") (part "C0805_IPCGEN"))
    )
    (comp (ref "C203")
      (value "22nF")
      (footprint "eagle-import:0805_IPC-7351B")
      (fields (field (name "PACKAGE") "0805") (field (name "VOLTAGE") "50V"))
      (libsource (lib "eagle-import") (part "C0805_IPCGEN"))
    )
    (comp (ref "C204")
      (value "27nF")
      (footprint "eagle-import:0805_IPC-7351B")
      (fields (field (name "PACKAGE") "0805") (field (name "VOLTAGE") "50V"))
      (libsource (lib "eagle-import") (part "C0805_IPCGEN"))
    )
    (comp (ref "C205")
      (value "DNP")
      (footprint "eagle-import:0805_IPC-7351B")
      (fields (field (name "BOM") "EXCLUDE") (field (name "VOLTAGE") "50V"))
      (libsource (lib "eagle-import") (part "C0805_IPCGEN"))
    )
    (comp (ref "C206")
      (value "DNP")
      (footprint "eagle-import:0805_IPC-7351B")
      (fields (field (name "BOM") "EXCLUDE") (field (name "VOLTAGE") "50V"))
      (libsource (lib "eagle-import") (part "C0805_IPCGEN"))
    )
    (comp (ref "C207")
      (value "DNP")
      (footprint "eagle-import:0805_IPC-7351B")
      (fields (field (name "BOM") "EXCLUDE") (field (name "VOLTAGE") "50V"))
      (libsource (lib "eagle-import") (part "C0805_IPCGEN"))
    )
    (comp (ref "C208")
      (value "DNP")
      (footprint "eagle-import:0805_IPC-7351B")
      (fields (field (name "BOM") "EXCLUDE") (field (name "VOLTAGE") "50V"))
      (libsource (lib "eagle-import") (part "C0805_IPCGEN"))
    )
    (comp (ref "C209")
      (value "2.2nF")
      (footprint "eagle-import:C1206")
      (fields (field (name "PACKAGE") "1206") (field (name "VOLTAGE") "100V"))
      (libsource (lib "eagle-import") (part "CC1206GEN"))
    )
    (comp (ref "C210")
      (value "2.2nF")
      (footprint "eagle-import:C1206")
      (fields (field (name "PACKAGE") "1206") (field (name "VOLTAGE") "100V"))
      (libsource (lib "eagle-import") (part "CC1206GEN"))
    )
    (comp (ref "C211")
      (value "10nF")
      (footprint "eagle-import:0805_IPC-7351B")
      (fields (field (name "VOLTAGE") "50V"))
      (libsource (lib "eagle-import") (part "C0805_IPCGEN"))
    )
    (comp (ref "C212")
      (value "10nF")
      (footprint "eagle-import:0805_IPC-7351B")
      (fields (field (name "VOLTAGE") "50V"))
      (libsource (lib "eagle-import") (part "C0805_IPCGEN"))
    )
    (comp (ref "L201")
      (value "47nH")
      (footprint "eagle-import:L1008")
      (fields (field (name "PARTNO") "1008CS-470XJLC"))
      (libsource (lib "eagle-import") (part "L_CHIP1008L-47N-AIR-5%-1008-1A"))
    )
    (comp (ref "L202")
      (value "47nH")
      (footprint "eagle-import:L1008")
      (fields (field (name "PARTNO") "1008CS-470XJLC"))
      (libsource (lib "eagle-import") (part "L_CHIP1008L-47N-AIR-5%-1008-1A"))
    )
    (comp (ref "Q201")
      (value "IRF630")
      (footprint "eagle-import:TO220BV")
      (fields (field (name "VOLTAGE") "200V"))
      (libsource (lib "eagle-import") (part "MOSFET_NTO-220-VERTIRF630"))
    )
    (comp (ref "Q202")
      (value "IRF630")
      (footprint "eagle-import:TO220BV")
      (fields (field (name "VOLTAGE") "200V"))
      (libsource (lib "eagle-import") (part "MOSFET_NTO-220-VERTIRF630"))
    )
    (comp (ref "R201")
      (value "75")
      (footprint "eagle-import:1206_IPC-7351B")
      (libsource (lib "eagle-import") (part "R1206_IPCGEN"))
    )
    (comp (ref "R202")
      (value "75")
      (footprint "eagle-import:1206_IPC-7351B")
      (libsource (lib "eagle-import") (part "R1206_IPCGEN"))
    )
    (comp (ref "R203")
      (value "4.99")
      (footprint "eagle-import:1206_IPC-7351B")
      (libsource (lib "eagle-import") (part "R901206_IPCGEN"))
    )
    (comp (ref "R204")
      (value "4.99")
      (footprint "eagle-import:1206_IPC-7351B")
      (libsource (lib "eagle-import") (part "R901206_IPCGEN"))
    )
    (comp (ref "R205")
      (value "75")
      (footprint "eagle-import:1206_IPC-7351B")
      (libsource (lib "eagle-import") (part "R1206_IPCGEN"))
    )
    (comp (ref "R206")
      (value "75")
      (footprint "eagle-import:1206_IPC-7351B")
      (libsource (lib "eagle-import") (part "R1206_IPCGEN"))
    )
    (comp (ref "R207")
      (value "100")
      (footprint "eagle-import:0805_IPC-7351B")
      (libsource (lib "eagle-import") (part "R0805_IPCGEN"))
    )
    (comp (ref "R208")
      (value "100")
      (footprint "eagle-import:1206_IPC-7351B")
      (libsource (lib "eagle-import") (part "R1206_IPCGEN"))
    )
    (comp (ref "R209")
      (value "100")
      (footprint "eagle-import:0805_IPC-7351B")
      (libsource (lib "eagle-import") (part "R0805_IPCGEN"))
    )
    (comp (ref "R210")
      (value "100")
      (footprint "eagle-import:1206_IPC-7351B")
      (libsource (lib "eagle-import") (part "R1206_IPCGEN"))
    )
    (comp (ref "R211")
      (value "DNP")
      (footprint "eagle-import:0805_IPC-7351B")
      (fields (field (name "BOM") "EXCLUDE"))
      (libsource (lib "eagle-import") (part "R0805_IPCGEN"))
    )
    (comp (ref "R212")
      (value "DNP")
      (footprint "eagle-import:0805_IPC-7351B")
      (fields (field (name "BOM") "EXCLUDE"))
      (libsource (lib "eagle-import") (part "R0805_IPCGEN"))
    )
    (comp (ref "R213")
      (value "15")
      (footprint "eagle-import:0805_IPC-7351B")
      (libsource (lib "eagle-import") (part "R900805_IPCGEN"))
    )
    (comp (ref "R214")
      (value "15")
      (footprint "eagle-import:0805_IPC-7351B")
      (libsource (lib "eagle-import") (part "R900805_IPCGEN"))
    )
    (comp (ref "R215")
      (value "DNP")
      (footprint "eagle-import:0805_IPC-7351B")
      (fields (field (name "BOM") "EXCLUDE"))
      (libsource (lib "eagle-import") (part "R0805_IPCGEN"))
    )
    (comp (ref "R216")
      (value "DNP")
      (footprint "eagle-import:0805_IPC-7351B")
      (fields (field (name "BOM") "EXCLUDE"))
      (libsource (lib "eagle-import") (part "R0805_IPCGEN"))
    )
    (comp (ref "R217")
      (value "330")
      (footprint "eagle-import:R2512")
      (libsource (lib "eagle-import") (part "R90R2512GEN"))
    )
    (comp (ref "R218")
      (value "270")
      (footprint "eagle-import:R2512")
      (libsource (lib "eagle-import") (part "R90R2512GEN"))
    )
    (comp (ref "R219")
      (value "330")
      (footprint "eagle-import:R2512")
      (libsource (lib "eagle-import") (part "R90R2512GEN"))
    )
    (comp (ref "R220")
      (value "270")
      (footprint "eagle-import:R2512")
      (libsource (lib "eagle-import") (part "R90R2512GEN"))
    )
    (comp (ref "R221")
      (value "2.7")
      (footprint "eagle-import:R2512")
      (libsource (lib "eagle-import") (part "RR2512GEN"))
    )
    (comp (ref "R222")
      (value "2.7")
      (footprint "eagle-import:R2512")
      (libsource (lib "eagle-import") (part "RR2512GEN"))
    )
    (comp (ref "R223")
      (value "2.7")
      (footprint "eagle-import:R2512")
      (libsource (lib "eagle-import") (part "RR2512GEN"))
    )
    (comp (ref "R224")
      (value "2.7")
      (footprint "eagle-import:R2512")
      (libsource (lib "eagle-import") (part "RR2512GEN"))
    )
    (comp (ref "R225")
      (value "2.7")
      (footprint "eagle-import:R2512")
      (libsource (lib "eagle-import") (part "RR2512GEN"))
    )
    (comp (ref "R226")
      (value "2.7")
      (footprint "eagle-import:R2512")
      (libsource (lib "eagle-import") (part "RR2512GEN"))
    )
    (comp (ref "R227")
      (value "3.3")
      (footprint "eagle-import:R2512")
      (libsource (lib "eagle-import") (part "RR2512GEN"))
    )
    (comp (ref "R228")
      (value "3.3")
      (footprint "eagle-import:R2512")
      (libsource (lib "eagle-import") (part "RR2512GEN"))
    )
    (comp (ref "R229")
      (value "1K")
      (footprint "eagle-import:0805_IPC-7351B")
      (libsource (lib "eagle-import") (part "R900805_IPCGEN"))
    )
    (comp (ref "R230")
      (value "1K")
      (footprint "eagle-import:0805_IPC-7351B")
      (libsource (lib "eagle-import") (part "R900805_IPCGEN"))
    )
    (comp (ref "TP7")
      (value "PROBE_TPTP_5MM")
      (footprint "eagle-import:PROBE_TP_5MM")
      (libsource (lib "eagle-import") (part "PROBE_TPTP_5MM"))
    )
    (comp (ref "TP8")
      (value "PROBE_TPTP_7P5MM")
      (footprint "eagle-import:PROBE_TP_7P5MM")
      (libsource (lib "eagle-import") (part "PROBE_TPTP_7P5MM"))
    )
    (comp (ref "TP9")
      (value "PROBE_TPTP_5MM")
      (footprint "eagle-import:PROBE_TP_5MM")
      (libsource (lib "eagle-import") (part "PROBE_TPTP_5MM"))
    )
    (comp (ref "TP10")
      (value "PROBE_TPTP_5MM")
      (footprint "eagle-import:PROBE_TP_5MM")
      (libsource (lib "eagle-import") (part "PROBE_TPTP_5MM"))
    )
    (comp (ref "TP16")
      (value "PROBE_TPTP_5MM")
      (footprint "eagle-import:PROBE_TP_5MM")
      (libsource (lib "eagle-import") (part "PROBE_TPTP_5MM"))
    )
    (comp (ref "TP17")
      (value "PROBE_TPTP_7P5MM")
      (footprint "eagle-import:PROBE_TP_7P5MM")
      (libsource (lib "eagle-import") (part "PROBE_TPTP_7P5MM"))
    )
  )
  (nets
    (net (code "1") (name "+5V") (class "Default")
      (node (ref "C306") (pin "1") (pinfunction "1_1") (pintype "passive"))
      (node (ref "C407") (pin "1") (pinfunction "1_1") (pintype "passive"))
      (node (ref "C410") (pin "+") (pinfunction "+_+") (pintype "passive"))
      (node (ref "LED301") (pin "A") (pinfunction "A_A") (pintype "passive"))
      (node (ref "LED402") (pin "A") (pinfunction "A_A") (pintype "passive"))
      (node (ref "R301") (pin "3") (pinfunction "E_3") (pintype "passive"))
      (node (ref "R408") (pin "1") (pinfunction "1_1") (pintype "passive"))
      (node (ref "U301") (pin "5") (pinfunction "VCC_5") (pintype "power_in"))
      (node (ref "U402") (pin "3") (pinfunction "OUT_3") (pintype "passive"))
    )
    (net (code "2") (name "ABN1") (class "Default")
      (node (ref "R103") (pin "1") (pinfunction "1_1") (pintype "passive"))
      (node (ref "R105") (pin "1") (pinfunction "1_1") (pintype "passive"))
      (node (ref "R202") (pin "1") (pinfunction "1_1") (pintype "passive"))
      (node (ref "R204") (pin "1") (pinfunction "1_1") (pintype "passive"))
      (node (ref "T101") (pin "11") (pinfunction "F2_11") (pintype "passive"))
      (node (ref "TP18") (pin "TP") (pinfunction "1_TP") (pintype "passive"))
    )
    (net (code "3") (name "ABP1") (class "Default")
      (node (ref "R102") (pin "1") (pinfunction "1_1") (pintype "passive"))
      (node (ref "R104") (pin "1") (pinfunction "1_1") (pintype "passive"))
      (node (ref "R201") (pin "1") (pinfunction "1_1") (pintype "passive"))
      (node (ref "R203") (pin "1") (pinfunction "1_1") (pintype "passive"))
      (node (ref "T101") (pin "1") (pinfunction "S1_1") (pintype "passive"))
      (node (ref "TP19") (pin "TP") (pinfunction "1_TP") (pintype "passive"))
    )
    (net (code "4") (name "AN2") (class "Default")
      (node (ref "C107") (pin "2") (pinfunction "2_2") (pintype "passive"))
      (node (ref "R105") (pin "2") (pinfunction "2_2") (pintype "passive"))
      (node (ref "R107") (pin "1") (pinfunction "1_1") (pintype "passive"))
    )
    (net (code "5") (name "AN3") (class "Default")
      (node (ref "C107") (pin "1") (pinfunction "1_1") (pintype "passive"))
      (node (ref "L102") (pin "1") (pinfunction "1_1") (pintype "passive"))
      (node (ref "R111") (pin "2") (pinfunction "2_2") (pintype "passive"))
      (node (ref "R113") (pin "1") (pinfunction "1_1") (pintype "passive"))
      (node (ref "R115") (pin "1") (pinfunction "1_1") (pintype "passive"))
    )
    (net (code "6") (name "AN4") (class "Default")
      (node (ref "L102") (pin "2") (pinfunction "2_2") (pintype "passive"))
      (node (ref "Q102") (pin "G") (pinfunction "G_G") (pintype "passive"))
      (node (ref "R115") (pin "2") (pinfunction "2_2") (pintype "passive"))
      (node (ref "R117") (pin "1") (pinfunction "1_1") (pintype "passive"))
      (node (ref "R120") (pin "1") (pinfunction "1_1") (pintype "passive"))
      (node (ref "R121") (pin "1") (pinfunction "1_1") (pintype "passive"))
      (node (ref "TP3") (pin "TP") (pinfunction "1_TP") (pintype "passive"))
    )
    (net (code "7") (name "AN5") (class "Default")
      (node (ref "Q102") (pin "S") (pinfunction "S_S") (pintype "passive"))
      (node (ref "R123") (pin "1") (pinfunction "1_1") (pintype "passive"))
      (node (ref "R125") (pin "1") (pinfunction "1_1") (pintype "passive"))
      (node (ref "R127") (pin "1") (pinfunction "1_1") (pintype "passive"))
      (node (ref "R129") (pin "1") (pinfunction "1_1") (pintype "passive"))
      (node (ref "R131") (pin "1") (pinfunction "1_1") (pintype "passive"))
      (node (ref "TP6") (pin "TP") (pinfunction "1_TP") (pintype "passive"))
    )
    (net (code "8") (name "AN6") (class "Default")
      (node (ref "C115") (pin "1") (pinfunction "1_1") (pintype "passive"))
      (node (ref "R131") (pin "2") (pinfunction "2_2") (pintype "passive"))
      (node (ref "TP15") (pin "TP") (pinfunction "1_TP") (pintype "passive"))
    )
    (net (code "9") (name "AP2") (class "Default")
      (node (ref "C105") (pin "2") (pinfunction "2_2") (pintype "passive"))
      (node (ref "R104") (pin "2") (pinfunction "2_2") (pintype "passive"))
      (node (ref "R106") (pin "1") (pinfunction "1_1") (pintype "passive"))
    )
    (net (code "10") (name "AP3") (class "Default")
      (node (ref "C105") (pin "1") (pinfunction "1_1") (pintype "passive"))
      (node (ref "L101") (pin "1") (pinfunction "1_1") (pintype "passive"))
      (node (ref "R109") (pin "2") (pinfunction "2_2") (pintype "passive"))
      (node (ref "R112") (pin "1") (pinfunction "1_1") (pintype "passive"))
      (node (ref "R114") (pin "1") (pinfunction "1_1") (pintype "passive"))
    )
    (net (code "11") (name "AP4") (class "Default")
      (node (ref "L101") (pin "2") (pinfunction "2_2") (pintype "passive"))
      (node (ref "Q101") (pin "G") (pinfunction "G_G") (pintype "passive"))
      (node (ref "R114") (pin "2") (pinfunction "2_2") (pintype "passive"))
      (node (ref "R116") (pin "1") (pinfunction "1_1") (pintype "passive"))
      (node (ref "R118") (pin "1") (pinfunction "1_1") (pintype "passive"))
      (node (ref "R119") (pin "1") (pinfunction "1_1") (pintype "passive"))
      (node (ref "TP1") (pin "TP") (pinfunction "1_TP") (pintype "passive"))
    )
    (net (code "12") (name "AP5") (class "Default")
      (node (ref "Q101") (pin "S") (pinfunction "S_S") (pintype "passive"))
      (node (ref "R122") (pin "1") (pinfunction "1_1") (pintype "passive"))
      (node (ref "R124") (pin "1") (pinfunction "1_1") (pintype "passive"))
      (node (ref "R126") (pin "1") (pinfunction "1_1") (pintype "passive"))
      (node (ref "R128") (pin "1") (pinfunction "1_1") (pintype "passive"))
      (node (ref "R130") (pin "1") (pinfunction "1_1") (pintype "passive"))
      (node (ref "TP5") (pin "TP") (pinfunction "1_TP") (pintype "passive"))
    )
    (net (code "13") (name "AP6") (class "Default")
      (node (ref "C114") (pin "1") (pinfunction "1_1") (pintype "passive"))
      (node (ref "R130") (pin "2") (pinfunction "2_2") (pintype "passive"))
      (node (ref "TP14") (pin "TP") (pinfunction "1_TP") (pintype "passive"))
    )
    (net (code "14") (name "BN2") (class "Default")
      (node (ref "C204") (pin "2") (pinfunction "2_2") (pintype "passive"))
      (node (ref "R204") (pin "2") (pinfunction "2_2") (pintype "passive"))
      (node (ref "R206") (pin "1") (pinfunction "1_1") (pintype "passive"))
    )
    (net (code "15") (name "BN3") (class "Default")
      (node (ref "C204") (pin "1") (pinfunction "1_1") (pintype "passive"))
      (node (ref "L202") (pin "1") (pinfunction "1_1") (pintype "passive"))
      (node (ref "R210") (pin "2") (pinfunction "2_2") (pintype "passive"))
      (node (ref "R212") (pin "1") (pinfunction "1_1") (pintype "passive"))
      (node (ref "R214") (pin "1") (pinfunction "1_1") (pintype "passive"))
    )
    (net (code "16") (name "BN4") (class "Default")
      (node (ref "L202") (pin "2") (pinfunction "2_2") (pintype "passive"))
      (node (ref "Q202") (pin "G") (pinfunction "G_G") (pintype "passive"))
      (node (ref "R214") (pin "2") (pinfunction "2_2") (pintype "passive"))
      (node (ref "R216") (pin "1") (pinfunction "1_1") (pintype "passive"))
      (node (ref "R219") (pin "1") (pinfunction "1_1") (pintype "passive"))
      (node (ref "R220") (pin "1") (pinfunction "1_1") (pintype "passive"))
      (node (ref "TP9") (pin "TP") (pinfunction "1_TP") (pintype "passive"))
    )
    (net (code "17") (name "BN5") (class "Default")
      (node (ref "Q202") (pin "S") (pinfunction "S_S") (pintype "passive"))
      (node (ref "R222") (pin "1") (pinfunction "1_1") (pintype "passive"))
      (node (ref "R224") (pin "1") (pinfunction "1_1") (pintype "passive"))
      (node (ref "R226") (pin "1") (pinfunction "1_1") (pintype "passive"))
      (node (ref "R228") (pin "1") (pinfunction "1_1") (pintype "passive"))
      (node (ref "R230") (pin "1") (pinfunction "1_1") (pintype "passive"))
      (node (ref "TP10") (pin "TP") (pinfunction "1_TP") (pintype "passive"))
    )
    (net (code "18") (name "BN6") (class "Default")
      (node (ref "C212") (pin "1") (pinfunction "1_1") (pintype "passive"))
      (node (ref "R230") (pin "2") (pinfunction "2_2") (pintype "passive"))
      (node (ref "TP17") (pin "TP") (pinfunction "1_TP") (pintype "passive"))
    )
    (net (code "19") (name "BP2") (class "Default")
      (node (ref "C202") (pin "2") (pinfunction "2_2") (pintype "passive"))
      (node (ref "R203") (pin "2") (pinfunction "2_2") (pintype "passive"))
      (node (ref "R205") (pin "1") (pinfunction "1_1") (pintype "passive"))
    )
    (net (code "20") (name "BP3") (class "Default")
      (node (ref "C202") (pin "1") (pinfunction "1_1") (pintype "passive"))
      (node (ref "L201") (pin "1") (pinfunction "1_1") (pintype "passive"))
      (node (ref "R208") (pin "2") (pinfunction "2_2") (pintype "passive"))
      (node (ref "R211") (pin "1") (pinfunction "1_1") (pintype "passive"))
      (node (ref "R213") (pin "1") (pinfunction "1_1") (pintype "passive"))
    )
    (net (code "21") (name "BP4") (class "Default")
      (node (ref "L201") (pin "2") (pinfunction "2_2") (pintype "passive"))
      (node (ref "Q201") (pin "G") (pinfunction "G_G") (pintype "passive"))
      (node (ref "R213") (pin "2") (pinfunction "2_2") (pintype "passive"))
      (node (ref "R215") (pin "1") (pinfunction "1_1") (pintype "passive"))
      (node (ref "R217") (pin "1") (pinfunction "1_1") (pintype "passive"))
      (node (ref "R218") (pin "1") (pinfunction "1_1") (pintype "passive"))
      (node (ref "TP7") (pin "TP") (pinfunction "1_TP") (pintype "passive"))
    )
    (net (code "22") (name "BP5") (class "Default")
      (node (ref "Q201") (pin "S") (pinfunction "S_S") (pintype "passive"))
      (node (ref "R221") (pin "1") (pinfunction "1_1") (pintype "passive"))
      (node (ref "R223") (pin "1") (pinfunction "1_1") (pintype "passive"))
      (node (ref "R225") (pin "1") (pinfunction "1_1") (pintype "passive"))
      (node (ref "R227") (pin "1") (pinfunction "1_1") (pintype "passive"))
      (node (ref "R229") (pin "1") (pinfunction "1_1") (pintype "passive"))
      (node (ref "TP8") (pin "TP") (pinfunction "1_TP") (pintype "passive"))
    )
    (net (code "23") (name "BP6") (class "Default")
      (node (ref "C211") (pin "1") (pinfunction "1_1") (pintype "passive"))
      (node (ref "R229") (pin "2") (pinfunction "2_2") (pintype "passive"))
      (node (ref "TP16") (pin "TP") (pinfunction "1_TP") (pintype "passive"))
    )
    (net (code "24") (name "DRAINS_NEG") (class "Default")
      (node (ref "C113") (pin "2") (pinfunction "2_2") (pintype "passive"))
      (node (ref "C117") (pin "2") (pinfunction "2_2") (pintype "passive"))
      (node (ref "C210") (pin "2") (pinfunction "2_2") (pintype "passive"))
      (node (ref "L104") (pin "1") (pinfunction "1_1") (pintype "passive"))
      (node (ref "Q102") (pin "D") (pinfunction "D_D") (pintype "passive"))
      (node (ref "Q202") (pin "D") (pinfunction "D_D") (pintype "passive"))
      (node (ref "T102") (pin "8") (pinfunction "F5_8") (pintype "passive"))
      (node (ref "TP4") (pin "TP") (pinfunction "1_TP") (pintype "passive"))
    )
    (net (code "25") (name "DRAINS_POS") (class "Default")
      (node (ref "C112") (pin "2") (pinfunction "2_2") (pintype "passive"))
      (node (ref "C116") (pin "2") (pinfunction "2_2") (pintype "passive"))
      (node (ref "C209") (pin "2") (pinfunction "2_2") (pintype "passive"))
      (node (ref "L103") (pin "1") (pinfunction "1_1") (pintype "passive"))
      (node (ref "Q101") (pin "D") (pinfunction "D_D") (pintype "passive"))
      (node (ref "Q201") (pin "D") (pinfunction "D_D") (pintype "passive"))
      (node (ref "T102") (pin "6") (pinfunction "S6_6") (pintype "passive"))
      (node (ref "TP2") (pin "TP") (pinfunction "1_TP") (pintype "passive"))
    )
    (net (code "26") (name "GBIAS") (class "Default")
      (node (ref "Q302") (pin "2") (pinfunction "E_2") (pintype "passive"))
      (node (ref "Q303") (pin "2") (pinfunction "E_2") (pintype "passive"))
      (node (ref "R108") (pin "1") (pinfunction "1_1") (pintype "passive"))
      (node (ref "R110") (pin "1") (pinfunction "1_1") (pintype "passive"))
      (node (ref "R207") (pin "1") (pinfunction "1_1") (pintype "passive"))
      (node (ref "R209") (pin "1") (pinfunction "1_1") (pintype "passive"))
      (node (ref "R316") (pin "2") (pinfunction "2_2") (pintype "passive"))
      (node (ref "R317") (pin "2") (pinfunction "2_2") (pintype "passive"))
      (node (ref "TP11") (pin "TP") (pinfunction "1_TP") (pintype "passive"))
    )
    (net (code "27") (name "Net-(C104-Pad1)") (class "Default")
      (node (ref "C104") (pin "1") (pinfunction "1_1") (pintype "passive"))
      (node (ref "R108") (pin "2") (pinfunction "2_2") (pintype "passive"))
      (node (ref "R109") (pin "1") (pinfunction "1_1") (pintype "passive"))
    )
    (net (code "28") (name "Net-(C106-Pad1)") (class "Default")
      (node (ref "C106") (pin "1") (pinfunction "1_1") (pintype "passive"))
      (node (ref "R110") (pin "2") (pinfunction "2_2") (pintype "passive"))
      (node (ref "R111") (pin "1") (pinfunction "1_1") (pintype "passive"))
    )
    (net (code "29") (name "Net-(C108-Pad1)") (class "Default")
      (node (ref "C108") (pin "1") (pinfunction "1_1") (pintype "passive"))
      (node (ref "R112") (pin "2") (pinfunction "2_2") (pintype "passive"))
    )
    (net (code "30") (name "Net-(C109-Pad1)") (class "Default")
      (node (ref "C109") (pin "1") (pinfunction "1_1") (pintype "passive"))
      (node (ref "R113") (pin "2") (pinfunction "2_2") (pintype "passive"))
    )
    (net (code "31") (name "Net-(C110-Pad1)") (class "Default")
      (node (ref "C110") (pin "1") (pinfunction "1_1") (pintype "passive"))
      (node (ref "R116") (pin "2") (pinfunction "2_2") (pintype "passive"))
    )
    (net (code "32") (name "Net-(C111-Pad1)") (class "Default")
      (node (ref "C111") (pin "1") (pinfunction "1_1") (pintype "passive"))
      (node (ref "R117") (pin "2") (pinfunction "2_2") (pintype "passive"))
    )
    (net (code "33") (name "Net-(C112-Pad1)") (class "Default")
      (node (ref "C112") (pin "1") (pinfunction "1_1") (pintype "passive"))
      (node (ref "R118") (pin "2") (pinfunction "2_2") (pintype "passive"))
      (node (ref "R119") (pin "2") (pinfunction "2_2") (pintype "passive"))
    )
    (net (code "34") (name "Net-(C113-Pad1)") (class "Default")
      (node (ref "C113") (pin "1") (pinfunction "1_1") (pintype "passive"))
      (node (ref "R120") (pin "2") (pinfunction "2_2") (pintype "passive"))
      (node (ref "R121") (pin "2") (pinfunction "2_2") (pintype "passive"))
    )
    (net (code "35") (name "Net-(C201-Pad1)") (class "Default")
      (node (ref "C201") (pin "1") (pinfunction "1_1") (pintype "passive"))
      (node (ref "R207") (pin "2") (pinfunction "2_2") (pintype "passive"))
      (node (ref "R208") (pin "1") (pinfunction "1_1") (pintype "passive"))
    )
    (net (code "36") (name "Net-(C203-Pad1)") (class "Default")
      (node (ref "C203") (pin "1") (pinfunction "1_1") (pintype "passive"))
      (node (ref "R209") (pin "2") (pinfunction "2_2") (pintype "passive"))
      (node (ref "R210") (pin "1") (pinfunction "1_1") (pintype "passive"))
    )
    (net (code "37") (name "Net-(C205-Pad1)") (class "Default")
      (node (ref "C205") (pin "1") (pinfunction "1_1") (pintype "passive"))
      (node (ref "R211") (pin "2") (pinfunction "2_2") (pintype "passive"))
    )
    (net (code "38") (name "Net-(C206-Pad1)") (class "Default")
      (node (ref "C206") (pin "1") (pinfunction "1_1") (pintype "passive"))
      (node (ref "R212") (pin "2") (pinfunction "2_2") (pintype "passive"))
    )
    (net (code "39") (name "Net-(C207-Pad1)") (class "Default")
      (node (ref "C207") (pin "1") (pinfunction "1_1") (pintype "passive"))
      (node (ref "R215") (pin "2") (pinfunction "2_2") (pintype "passive"))
    )
    (net (code "40") (name "Net-(C208-Pad1)") (class "Default")
      (node (ref "C208") (pin "1") (pinfunction "1_1") (pintype "passive"))
      (node (ref "R216") (pin "2") (pinfunction "2_2") (pintype "passive"))
    )
    (net (code "41") (name "Net-(C209-Pad1)") (class "Default")
      (node (ref "C209") (pin "1") (pinfunction "1_1") (pintype "passive"))
      (node (ref "R217") (pin "2") (pinfunction "2_2") (pintype "passive"))
      (node (ref "R218") (pin "2") (pinfunction "2_2") (pintype "passive"))
    )
    (net (code "42") (name "Net-(C210-Pad1)") (class "Default")
      (node (ref "C210") (pin "1") (pinfunction "1_1") (pintype "passive"))
      (node (ref "R219") (pin "2") (pinfunction "2_2") (pintype "passive"))
      (node (ref "R220") (pin "2") (pinfunction "2_2") (pintype "passive"))
    )
    (net (code "43") (name "Net-(C302-Pad1)") (class "Default")
      (node (ref "C302") (pin "1") (pinfunction "1_1") (pintype "passive"))
      (node (ref "R313") (pin "1") (pinfunction "1_1") (pintype "passive"))
    )
    (net (code "44") (name "Net-(C304-Pad1)") (class "Default")
      (node (ref "C304") (pin "1") (pinfunction "1_1") (pintype "passive"))
      (node (ref "R314") (pin "2") (pinfunction "2_2") (pintype "passive"))
    )
    (net (code "45") (name "Net-(C405-Pad1)") (class "Default")
      (node (ref "C405") (pin "1") (pinfunction "1_1") (pintype "passive"))
      (node (ref "L401") (pin "2") (pinfunction "2_2") (pintype "passive"))
      (node (ref "L402") (pin "1") (pinfunction "1_1") (pintype "passive"))
      (node (ref "R404") (pin "1") (pinfunction "1_1") (pintype "passive"))
      (node (ref "R405") (pin "1") (pinfunction "1_1") (pintype "passive"))
    )
    (net (code "46") (name "Net-(D401-C1)") (class "Default")
      (node (ref "D401") (pin "K") (pinfunction "C1_K") (pintype "passive"))
      (node (ref "F401") (pin "2") (pinfunction "2_2") (pintype "passive"))
      (node (ref "R401") (pin "1") (pinfunction "1_1") (pintype "passive"))
    )
    (net (code "47") (name "Net-(D402-A1)") (class "Default")
      (node (ref "D402") (pin "A") (pinfunction "A1_A") (pintype "passive"))
      (node (ref "R402") (pin "1") (pinfunction "1_1") (pintype "passive"))
      (node (ref "R403") (pin "1") (pinfunction "1_1") (pintype "passive"))
    )
    (net (code "48") (name "Net-(D402-C1)") (class "Default")
      (node (ref "C401") (pin "+") (pinfunction "+_+") (pintype "passive"))
      (node (ref "C402") (pin "1") (pinfunction "1_1") (pintype "passive"))
      (node (ref "D402") (pin "C") (pinfunction "C1_C") (pintype "passive"))
      (node (ref "L401") (pin "1") (pinfunction "1_1") (pintype "passive"))
      (node (ref "R401") (pin "2") (pinfunction "2_2") (pintype "passive"))
    )
    (net (code "49") (name "Net-(F401-Pad1)") (class "Default")
      (node (ref "F401") (pin "1") (pinfunction "1_1") (pintype "passive"))
      (node (ref "J401") (pin "1") (pinfunction "1_1") (pintype "passive"))
    )
    (net (code "50") (name "Net-(J101-1)") (class "Default")
      (node (ref "C101") (pin "2") (pinfunction "2_2") (pintype "passive"))
      (node (ref "C102") (pin "2") (pinfunction "2_2") (pintype "passive"))
      (node (ref "C103") (pin "2") (pinfunction "2_2") (pintype "passive"))
      (node (ref "J101") (pin "C") (pinfunction "1_C") (pintype "passive"))
    )
    (net (code "51") (name "Net-(J102-1)") (class "Default")
      (node (ref "C118") (pin "2") (pinfunction "2_2") (pintype "passive"))
      (node (ref "C119") (pin "2") (pinfunction "2_2") (pintype "passive"))
      (node (ref "C120") (pin "2") (pinfunction "2_2") (pintype "passive"))
      (node (ref "J102") (pin "C") (pinfunction "1_C") (pintype "passive"))
    )
    (net (code "52") (name "Net-(J301-1)") (class "Default")
      (node (ref "J301") (pin "C") (pinfunction "1_C") (pintype "passive"))
      (node (ref "JP301") (pin "2") (pinfunction "2_2") (pintype "passive"))
      (node (ref "R302") (pin "1") (pinfunction "1_1") (pintype "passive"))
    )
    (net (code "53") (name "Net-(J301-GND1-PadG1)") (class "Default")
      (node (ref "J301") (pin "G1") (pinfunction "GND1_G1") (pintype "power_in"))
      (node (ref "J301") (pin "G2") (pinfunction "GND1_G2") (pintype "power_in"))
      (node (ref "J301") (pin "G3") (pinfunction "GND1_G3") (pintype "power_in"))
      (node (ref "J301") (pin "G4") (pinfunction "GND1_G4") (pintype "power_in"))
      (node (ref "JP301") (pin "1") (pinfunction "1_1") (pintype "passive"))
      (node (ref "R303") (pin "1") (pinfunction "1_1") (pintype "passive"))
    )
    (net (code "54") (name "Net-(J302-1)") (class "Default")
      (node (ref "J302") (pin "C") (pinfunction "1_C") (pintype "passive"))
      (node (ref "R304") (pin "1") (pinfunction "1_1") (pintype "passive"))
    )
    (net (code "55") (name "Net-(J402-Pad3)") (class "Default")
      (node (ref "J402") (pin "3") (pinfunction "3_3") (pintype "passive"))
      (node (ref "R408") (pin "2") (pinfunction "2_2") (pintype "passive"))
    )
    (net (code "56") (name "Net-(LED301-C)") (class "Default")
      (node (ref "LED301") (pin "K") (pinfunction "C_K") (pintype "passive"))
      (node (ref "R309") (pin "1") (pinfunction "1_1") (pintype "passive"))
    )
    (net (code "57") (name "Net-(LED401-C)") (class "Default")
      (node (ref "LED401") (pin "K") (pinfunction "C_K") (pintype "passive"))
      (node (ref "R406") (pin "1") (pinfunction "1_1") (pintype "passive"))
    )
    (net (code "58") (name "Net-(LED402-C)") (class "Default")
      (node (ref "LED402") (pin "K") (pinfunction "C_K") (pintype "passive"))
      (node (ref "R407") (pin "1") (pinfunction "1_1") (pintype "passive"))
    )
    (net (code "59") (name "Net-(Q301-D)") (class "Default")
      (node (ref "Q301") (pin "3") (pinfunction "D_3") (pintype "passive"))
      (node (ref "R308") (pin "2") (pinfunction "2_2") (pintype "passive"))
      (node (ref "U302") (pin "5") (pinfunction "+IN_5") (pintype "input"))
    )
    (net (code "60") (name "Net-(Q301-G)") (class "Default")
      (node (ref "Q301") (pin "1") (pinfunction "G_1") (pintype "passive"))
      (node (ref "R309") (pin "2") (pinfunction "2_2") (pintype "passive"))
      (node (ref "U301") (pin "4") (pinfunction "O_4") (pintype "output"))
    )
    (net (code "61") (name "Net-(Q302-B)") (class "Default")
      (node (ref "Q302") (pin "1") (pinfunction "B_1") (pintype "passive"))
      (node (ref "Q303") (pin "1") (pinfunction "B_1") (pintype "passive"))
      (node (ref "R315") (pin "2") (pinfunction "2_2") (pintype "passive"))
      (node (ref "R316") (pin "1") (pinfunction "1_1") (pintype "passive"))
    )
    (net (code "62") (name "Net-(R301-S)") (class "Default")
      (node (ref "C301") (pin "1") (pinfunction "1_1") (pintype "passive"))
      (node (ref "R301") (pin "2") (pinfunction "S_2") (pintype "passive"))
      (node (ref "U302") (pin "12") (pinfunction "+IN_12") (pintype "input"))
    )
    (net (code "63") (name "Net-(T101-F1)") (class "Default")
      (node (ref "R101") (pin "1") (pinfunction "1_1") (pintype "passive"))
      (node (ref "T101") (pin "12") (pinfunction "F1_12") (pintype "passive"))
      (node (ref "T101") (pin "2") (pinfunction "S2_2") (pintype "passive"))
    )
    (net (code "64") (name "Net-(T101-F4)") (class "Default")
      (node (ref "T101") (pin "3") (pinfunction "S3_3") (pintype "passive"))
      (node (ref "T101") (pin "9") (pinfunction "F4_9") (pintype "passive"))
    )
    (net (code "65") (name "Net-(T101-F5)") (class "Default")
      (node (ref "C101") (pin "1") (pinfunction "1_1") (pintype "passive"))
      (node (ref "T101") (pin "4") (pinfunction "S4_4") (pintype "passive"))
      (node (ref "T101") (pin "8") (pinfunction "F5_8") (pintype "passive"))
    )
    (net (code "66") (name "Net-(T101-F6)") (class "Default")
      (node (ref "C102") (pin "1") (pinfunction "1_1") (pintype "passive"))
      (node (ref "T101") (pin "5") (pinfunction "S5_5") (pintype "passive"))
      (node (ref "T101") (pin "7") (pinfunction "F6_7") (pintype "passive"))
    )
    (net (code "67") (name "Net-(T101-S6)") (class "Default")
      (node (ref "C103") (pin "1") (pinfunction "1_1") (pintype "passive"))
      (node (ref "T101") (pin "6") (pinfunction "S6_6") (pintype "passive"))
    )
    (net (code "68") (name "Net-(T102-F1)") (class "Default")
      (node (ref "C119") (pin "1") (pinfunction "1_1") (pintype "passive"))
      (node (ref "T102") (pin "12") (pinfunction "F1_12") (pintype "passive"))
      (node (ref "T102") (pin "2") (pinfunction "S2_2") (pintype "passive"))
    )
    (net (code "69") (name "Net-(T102-F2)") (class "Default")
      (node (ref "C118") (pin "1") (pinfunction "1_1") (pintype "passive"))
      (node (ref "T102") (pin "11") (pinfunction "F2_11") (pintype "passive"))
      (node (ref "T102") (pin "3") (pinfunction "S3_3") (pintype "passive"))
    )
    (net (code "70") (name "Net-(T102-F3)") (class "Default")
      (node (ref "T102") (pin "10") (pinfunction "F3_10") (pintype "passive"))
      (node (ref "T102") (pin "4") (pinfunction "S4_4") (pintype "passive"))
    )
    (net (code "71") (name "Net-(T102-F6)") (class "Default")
      (node (ref "R132") (pin "2") (pinfunction "2_2") (pintype "passive"))
      (node (ref "T102") (pin "5") (pinfunction "S5_5") (pintype "passive"))
      (node (ref "T102") (pin "7") (pinfunction "F6_7") (pintype "passive"))
    )
    (net (code "72") (name "Net-(T102-S1)") (class "Default")
      (node (ref "C120") (pin "1") (pinfunction "1_1") (pintype "passive"))
      (node (ref "T102") (pin "1") (pinfunction "S1_1") (pintype "passive"))
    )
    (net (code "73") (name "Net-(TP12-1)") (class "Default")
      (node (ref "R310") (pin "1") (pinfunction "1_1") (pintype "passive"))
      (node (ref "TP12") (pin "TP") (pinfunction "1_TP") (pintype "passive"))
      (node (ref "U302") (pin "6") (pinfunction "-IN_6") (pintype "input"))
      (node (ref "U302") (pin "7") (pinfunction "OUT_7") (pintype "output"))
    )
    (net (code "74") (name "Net-(TP13-1)") (class "Default")
      (node (ref "R306") (pin "2") (pinfunction "2_2") (pintype "passive"))
      (node (ref "TP13") (pin "TP") (pinfunction "1_TP") (pintype "passive"))
      (node (ref "U302") (pin "13") (pinfunction "-IN_13") (pintype "input"))
      (node (ref "U302") (pin "14") (pinfunction "OUT_14") (pintype "output"))
    )
    (net (code "75") (name "Net-(U301A-I)") (class "Default")
      (node (ref "R304") (pin "2") (pinfunction "2_2") (pintype "passive"))
      (node (ref "R307") (pin "1") (pinfunction "1_1") (pintype "passive"))
      (node (ref "U301") (pin "2") (pinfunction "I_2") (pintype "input"))
    )
    (net (code "76") (name "Net-(U302A-+IN)") (class "Default")
      (node (ref "C303") (pin "1") (pinfunction "1_1") (pintype "passive"))
      (node (ref "R310") (pin "2") (pinfunction "2_2") (pintype "passive"))
      (node (ref "R311") (pin "1") (pinfunction "1_1") (pintype "passive"))
      (node (ref "U302") (pin "3") (pinfunction "+IN_3") (pintype "input"))
    )
    (net (code "77") (name "Net-(U302A--IN)") (class "Default")
      (node (ref "C304") (pin "2") (pinfunction "2_2") (pintype "passive"))
      (node (ref "R312") (pin "2") (pinfunction "2_2") (pintype "passive"))
      (node (ref "R313") (pin "2") (pinfunction "2_2") (pintype "passive"))
      (node (ref "R317") (pin "1") (pinfunction "1_1") (pintype "passive"))
      (node (ref "U302") (pin "2") (pinfunction "-IN_2") (pintype "input"))
    )
    (net (code "78") (name "Net-(U302A-OUT)") (class "Default")
      (node (ref "R314") (pin "1") (pinfunction "1_1") (pintype "passive"))
      (node (ref "R315") (pin "1") (pinfunction "1_1") (pintype "passive"))
      (node (ref "U302") (pin "1") (pinfunction "OUT_1") (pintype "output"))
    )
    (net (code "79") (name "Net-(U302C-+IN)") (class "Default")
      (node (ref "R303") (pin "2") (pinfunction "2_2") (pintype "passive"))
      (node (ref "R306") (pin "1") (pinfunction "1_1") (pintype "passive"))
      (node (ref "U302") (pin "10") (pinfunction "+IN_10") (pintype "input"))
    )
    (net (code "80") (name "Net-(U302C--IN)") (class "Default")
      (node (ref "JP302") (pin "1") (pinfunction "1_1") (pintype "passive"))
      (node (ref "R302") (pin "2") (pinfunction "2_2") (pintype "passive"))
      (node (ref "R305") (pin "1") (pinfunction "1_1") (pintype "passive"))
      (node (ref "U302") (pin "9") (pinfunction "-IN_9") (pintype "input"))
    )
    (net (code "81") (name "Net-(U302C-OUT)") (class "Default")
      (node (ref "JP302") (pin "2") (pinfunction "2_2") (pintype "passive"))
      (node (ref "R305") (pin "2") (pinfunction "2_2") (pintype "passive"))
      (node (ref "R308") (pin "1") (pinfunction "1_1") (pintype "passive"))
      (node (ref "U302") (pin "8") (pinfunction "OUT_8") (pintype "output"))
    )
    (net (code "82") (name "Net-(U401-IN)") (class "Default")
      (node (ref "C403") (pin "1") (pinfunction "1_1") (pintype "passive"))
      (node (ref "R402") (pin "2") (pinfunction "2_2") (pintype "passive"))
      (node (ref "U401") (pin "1") (pinfunction "IN_1") (pintype "input"))
    )
    (net (code "83") (name "Net-(U402-IN)") (class "Default")
      (node (ref "C404") (pin "1") (pinfunction "1_1") (pintype "passive"))
      (node (ref "R403") (pin "2") (pinfunction "2_2") (pintype "passive"))
      (node (ref "U402") (pin "1") (pinfunction "IN_1") (pintype "input"))
    )
    (net (code "84") (name "V+") (class "Default")
      (node (ref "C305") (pin "1") (pinfunction "1_1") (pintype "passive"))
      (node (ref "C406") (pin "1") (pinfunction "1_1") (pintype "passive"))
      (node (ref "C409") (pin "+") (pinfunction "+_+") (pintype "passive"))
      (node (ref "J402") (pin "2") (pinfunction "2_2") (pintype "passive"))
      (node (ref "LED401") (pin "A") (pinfunction "A_A") (pintype "passive"))
      (node (ref "Q303") (pin "3") (pinfunction "C_3") (pintype "passive"))
      (node (ref "U302") (pin "4") (pinfunction "V+_4") (pintype "power_in"))
      (node (ref "U401") (pin "3") (pinfunction "OUT_3") (pintype "passive"))
    )
    (net (code "85") (name "V-") (class "Default")
      (node (ref "C104") (pin "2") (pinfunction "2_2") (pintype "passive"))
      (node (ref "C106") (pin "2") (pinfunction "2_2") (pintype "passive"))
      (node (ref "C108") (pin "2") (pinfunction "2_2") (pintype "passive"))
      (node (ref "C109") (pin "2") (pinfunction "2_2") (pintype "passive"))
      (node (ref "C110") (pin "2") (pinfunction "2_2") (pintype "passive"))
      (node (ref "C111") (pin "2") (pinfunction "2_2") (pintype "passive"))
      (node (ref "C114") (pin "2") (pinfunction "2_2") (pintype "passive"))
      (node (ref "C115") (pin "2") (pinfunction "2_2") (pintype "passive"))
      (node (ref "C201") (pin "2") (pinfunction "2_2") (pintype "passive"))
      (node (ref "C203") (pin "2") (pinfunction "2_2") (pintype "passive"))
      (node (ref "C205") (pin "2") (pinfunction "2_2") (pintype "passive"))
      (node (ref "C206") (pin "2") (pinfunction "2_2") (pintype "passive"))
      (node (ref "C207") (pin "2") (pinfunction "2_2") (pintype "passive"))
      (node (ref "C208") (pin "2") (pinfunction "2_2") (pintype "passive"))
      (node (ref "C211") (pin "2") (pinfunction "2_2") (pintype "passive"))
      (node (ref "C212") (pin "2") (pinfunction "2_2") (pintype "passive"))
      (node (ref "C301") (pin "2") (pinfunction "2_2") (pintype "passive"))
      (node (ref "C302") (pin "2") (pinfunction "2_2") (pintype "passive"))
      (node (ref "C303") (pin "2") (pinfunction "2_2") (pintype "passive"))
      (node (ref "C305") (pin "2") (pinfunction "2_2") (pintype "passive"))
      (node (ref "C306") (pin "2") (pinfunction "2_2") (pintype "passive"))
      (node (ref "C401") (pin "-") (pinfunction "-_-") (pintype "passive"))
      (node (ref "C402") (pin "2") (pinfunction "2_2") (pintype "passive"))
      (node (ref "C403") (pin "2") (pinfunction "2_2") (pintype "passive"))
      (node (ref "C404") (pin "2") (pinfunction "2_2") (pintype "passive"))
      (node (ref "C405") (pin "2") (pinfunction "2_2") (pintype "passive"))
      (node (ref "C406") (pin "2") (pinfunction "2_2") (pintype "passive"))
      (node (ref "C407") (pin "2") (pinfunction "2_2") (pintype "passive"))
      (node (ref "C408") (pin "2") (pinfunction "2_2") (pintype "passive"))
      (node (ref "C409") (pin "-") (pinfunction "-_-") (pintype "passive"))
      (node (ref "C410") (pin "-") (pinfunction "-_-") (pintype "passive"))
      (node (ref "C411") (pin "2") (pinfunction "2_2") (pintype "passive"))
      (node (ref "C412") (pin "2") (pinfunction "2_2") (pintype "passive"))
      (node (ref "C413") (pin "2") (pinfunction "2_2") (pintype "passive"))
      (node (ref "D401") (pin "A") (pinfunction "A1_A") (pintype "passive"))
      (node (ref "H401") (pin "B3,2") (pinfunction "MOUNT_B3,2") (pintype "passive"))
      (node (ref "H402") (pin "B3,2") (pinfunction "MOUNT_B3,2") (pintype "passive"))
      (node (ref "H403") (pin "B3,2") (pinfunction "MOUNT_B3,2") (pintype "passive"))
      (node (ref "H404") (pin "B3,2") (pinfunction "MOUNT_B3,2") (pintype "passive"))
      (node (ref "J101") (pin "G1") (pinfunction "GND1_G1") (pintype "power_in"))
      (node (ref "J101") (pin "G2") (pinfunction "GND1_G2") (pintype "power_in"))
      (node (ref "J101") (pin "G3") (pinfunction "GND1_G3") (pintype "power_in"))
      (node (ref "J101") (pin "G4") (pinfunction "GND1_G4") (pintype "power_in"))
      (node (ref "J102") (pin "G1") (pinfunction "GND1_G1") (pintype "power_in"))
      (node (ref "J102") (pin "G2") (pinfunction "GND1_G2") (pintype "power_in"))
      (node (ref "J102") (pin "G3") (pinfunction "GND1_G3") (pintype "power_in"))
      (node (ref "J102") (pin "G4") (pinfunction "GND1_G4") (pintype "power_in"))
      (node (ref "J302") (pin "G1") (pinfunction "GND1_G1") (pintype "power_in"))
      (node (ref "J302") (pin "G2") (pinfunction "GND1_G2") (pintype "power_in"))
      (node (ref "J302") (pin "G3") (pinfunction "GND1_G3") (pintype "power_in"))
      (node (ref "J302") (pin "G4") (pinfunction "GND1_G4") (pintype "power_in"))
      (node (ref "J401") (pin "2") (pinfunction "2_2") (pintype "passive"))
      (node (ref "J402") (pin "1") (pinfunction "1_1") (pintype "passive"))
      (node (ref "Q301") (pin "2") (pinfunction "S_2") (pintype "passive"))
      (node (ref "Q302") (pin "3") (pinfunction "C_3") (pintype "passive"))
      (node (ref "R101") (pin "2") (pinfunction "2_2") (pintype "passive"))
      (node (ref "R102") (pin "2") (pinfunction "2_2") (pintype "passive"))
      (node (ref "R103") (pin "2") (pinfunction "2_2") (pintype "passive"))
      (node (ref "R106") (pin "2") (pinfunction "2_2") (pintype "passive"))
      (node (ref "R107") (pin "2") (pinfunction "2_2") (pintype "passive"))
      (node (ref "R122") (pin "2") (pinfunction "2_2") (pintype "passive"))
      (node (ref "R123") (pin "2") (pinfunction "2_2") (pintype "passive"))
      (node (ref "R124") (pin "2") (pinfunction "2_2") (pintype "passive"))
      (node (ref "R125") (pin "2") (pinfunction "2_2") (pintype "passive"))
      (node (ref "R126") (pin "2") (pinfunction "2_2") (pintype "passive"))
      (node (ref "R127") (pin "2") (pinfunction "2_2") (pintype "passive"))
      (node (ref "R128") (pin "2") (pinfunction "2_2") (pintype "passive"))
      (node (ref "R129") (pin "2") (pinfunction "2_2") (pintype "passive"))
      (node (ref "R201") (pin "2") (pinfunction "2_2") (pintype "passive"))
      (node (ref "R202") (pin "2") (pinfunction "2_2") (pintype "passive"))
      (node (ref "R205") (pin "2") (pinfunction "2_2") (pintype "passive"))
      (node (ref "R206") (pin "2") (pinfunction "2_2") (pintype "passive"))
      (node (ref "R221") (pin "2") (pinfunction "2_2") (pintype "passive"))
      (node (ref "R222") (pin "2") (pinfunction "2_2") (pintype "passive"))
      (node (ref "R223") (pin "2") (pinfunction "2_2") (pintype "passive"))
      (node (ref "R224") (pin "2") (pinfunction "2_2") (pintype "passive"))
      (node (ref "R225") (pin "2") (pinfunction "2_2") (pintype "passive"))
      (node (ref "R226") (pin "2") (pinfunction "2_2") (pintype "passive"))
      (node (ref "R227") (pin "2") (pinfunction "2_2") (pintype "passive"))
      (node (ref "R228") (pin "2") (pinfunction "2_2") (pintype "passive"))
      (node (ref "R301") (pin "1") (pinfunction "A_1") (pintype "passive"))
      (node (ref "R307") (pin "2") (pinfunction "2_2") (pintype "passive"))
      (node (ref "R311") (pin "2") (pinfunction "2_2") (pintype "passive"))
      (node (ref "R312") (pin "1") (pinfunction "1_1") (pintype "passive"))
      (node (ref "R406") (pin "2") (pinfunction "2_2") (pintype "passive"))
      (node (ref "R407") (pin "2") (pinfunction "2_2") (pintype "passive"))
      (node (ref "T101") (pin "10") (pinfunction "F3_10") (pintype "passive"))
      (node (ref "T102") (pin "9") (pinfunction "F4_9") (pintype "passive"))
      (node (ref "TP1") (pin "GND") (pinfunction "GND1_GND") (pintype "power_in"))
      (node (ref "TP10") (pin "GND") (pinfunction "GND1_GND") (pintype "power_in"))
      (node (ref "TP11") (pin "GND") (pinfunction "GND1_GND") (pintype "power_in"))
      (node (ref "TP12") (pin "GND") (pinfunction "GND1_GND") (pintype "power_in"))
      (node (ref "TP13") (pin "GND") (pinfunction "GND1_GND") (pintype "power_in"))
      (node (ref "TP14") (pin "GND") (pinfunction "GND1_GND") (pintype "power_in"))
      (node (ref "TP15") (pin "GND") (pinfunction "GND1_GND") (pintype "power_in"))
      (node (ref "TP16") (pin "GND") (pinfunction "GND1_GND") (pintype "power_in"))
      (node (ref "TP17") (pin "GND") (pinfunction "GND1_GND") (pintype "power_in"))
      (node (ref "TP18") (pin "GND") (pinfunction "GND1_GND") (pintype "power_in"))
      (node (ref "TP19") (pin "GND") (pinfunction "GND1_GND") (pintype "power_in"))
      (node (ref "TP2") (pin "GND") (pinfunction "GND1_GND") (pintype "power_in"))
      (node (ref "TP3") (pin "GND") (pinfunction "GND1_GND") (pintype "power_in"))
      (node (ref "TP4") (pin "GND") (pinfunction "GND1_GND") (pintype "power_in"))
      (node (ref "TP5") (pin "GND") (pinfunction "GND1_GND") (pintype "power_in"))
      (node (ref "TP6") (pin "GND") (pinfunction "GND1_GND") (pintype "power_in"))
      (node (ref "TP7") (pin "GND") (pinfunction "GND1_GND") (pintype "power_in"))
      (node (ref "TP8") (pin "GND") (pinfunction "GND1_GND") (pintype "power_in"))
      (node (ref "TP9") (pin "GND") (pinfunction "GND1_GND") (pintype "power_in"))
      (node (ref "U301") (pin "3") (pinfunction "GND_3") (pintype "power_in"))
      (node (ref "U302") (pin "11") (pinfunction "V-_11") (pintype "power_in"))
      (node (ref "U401") (pin "2") (pinfunction "GND_2") (pintype "input"))
      (node (ref "U402") (pin "2") (pinfunction "GND_2") (pintype "input"))
      (node (ref "X402") (pin "P1") (pinfunction "P$1_P1") (pintype "bidirectional"))
      (node (ref "X402") (pin "P2") (pinfunction "P$2_P2") (pintype "bidirectional"))
    )
    (net (code "86") (name "VB") (class "Default")
      (node (ref "C116") (pin "1") (pinfunction "1_1") (pintype "passive"))
      (node (ref "C117") (pin "1") (pinfunction "1_1") (pintype "passive"))
      (node (ref "C408") (pin "1") (pinfunction "1_1") (pintype "passive"))
      (node (ref "C411") (pin "1") (pinfunction "1_1") (pintype "passive"))
      (node (ref "C412") (pin "1") (pinfunction "1_1") (pintype "passive"))
      (node (ref "C413") (pin "1") (pinfunction "1_1") (pintype "passive"))
      (node (ref "L103") (pin "2") (pinfunction "2_2") (pintype "passive"))
      (node (ref "L104") (pin "2") (pinfunction "2_2") (pintype "passive"))
      (node (ref "L402") (pin "2") (pinfunction "2_2") (pintype "passive"))
      (node (ref "R132") (pin "1") (pinfunction "1_1") (pintype "passive"))
      (node (ref "R404") (pin "2") (pinfunction "2_2") (pintype "passive"))
      (node (ref "R405") (pin "2") (pinfunction "2_2") (pintype "passive"))
    )
    (net (code "87") (name "unconnected-(J402-Pad4)") (class "Default")
      (node (ref "J402") (pin "4") (pinfunction "4_4") (pintype "passive"))
    )
  )
)
